# Nucleo_PCB_V1_1.net
KiCad netlist of a schematic drawn in Altium Designer
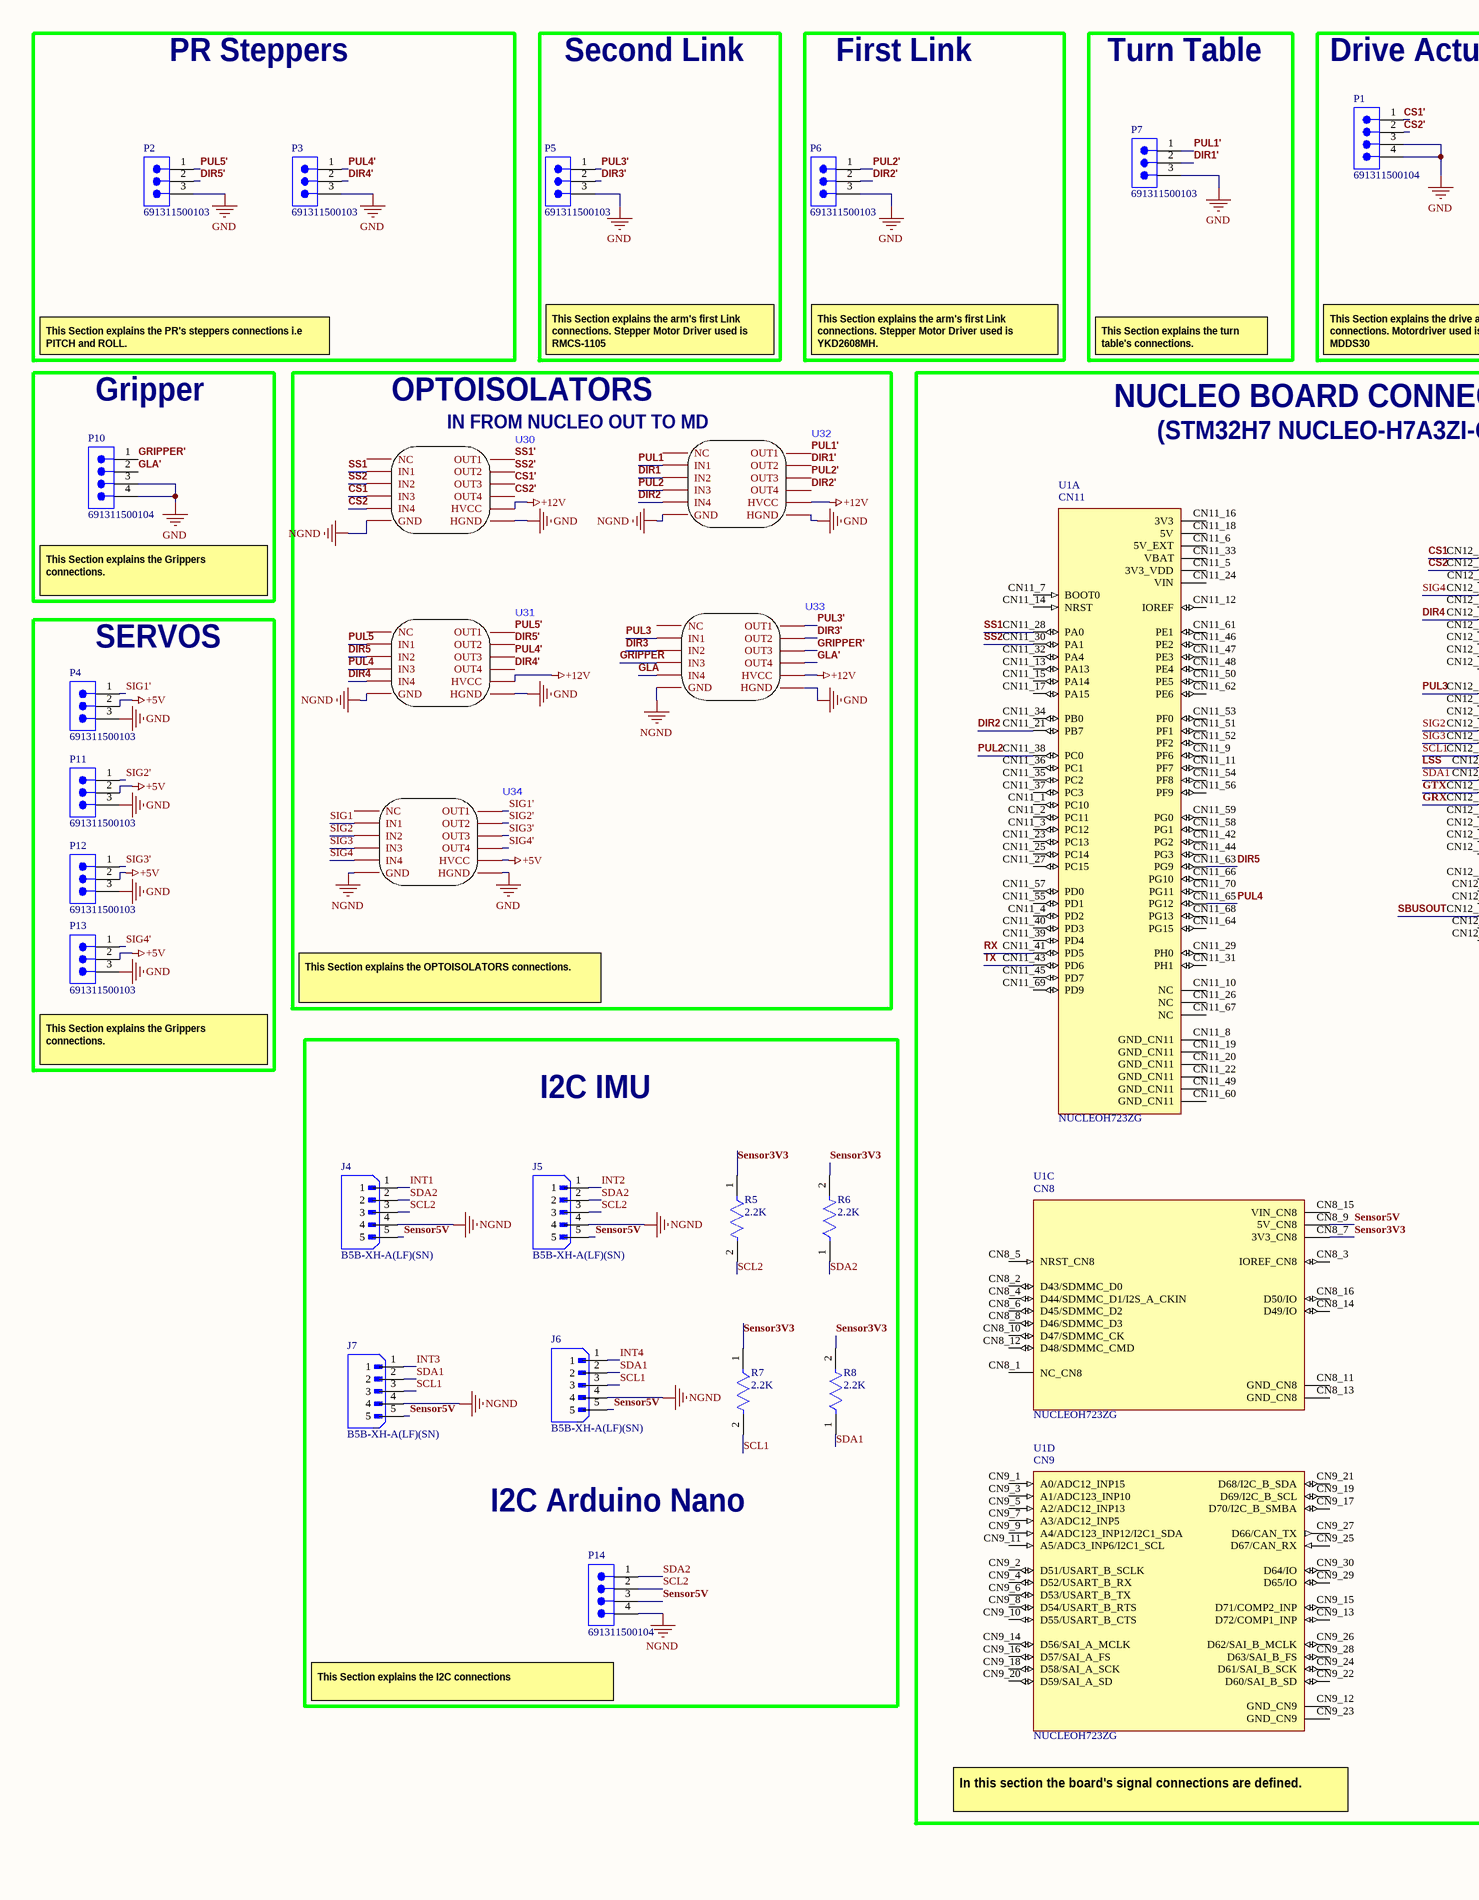
[diagram p0: Nucleo PCB V1.1.SchDoc, left]
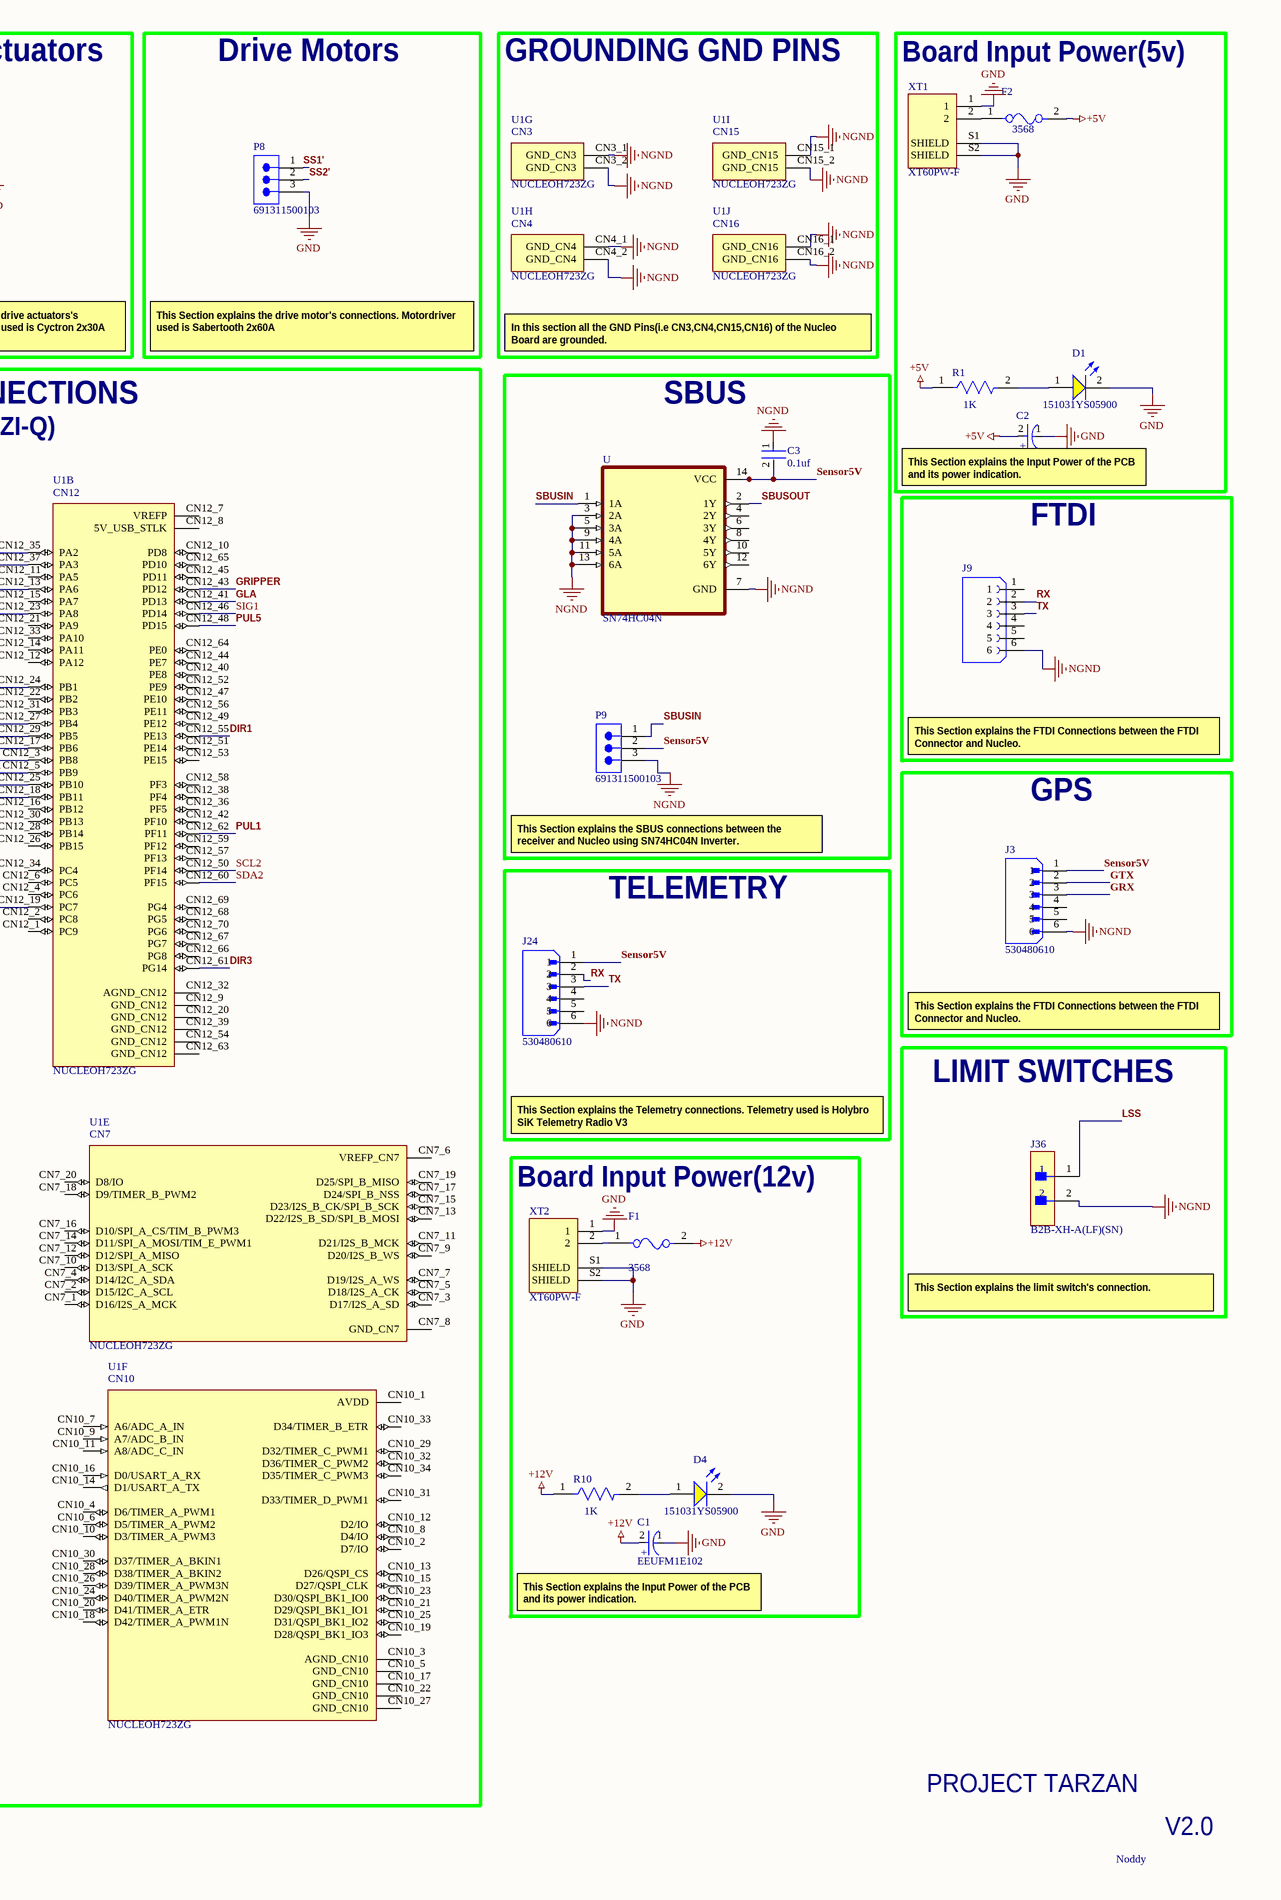
[diagram p1: Nucleo PCB V1.1.SchDoc, right]

(export (version "E")
  (design (tool "Eeschema 10.0.6"))
  (components
    (comp (ref "C1")
      (value "EEUFM1E102")
      (footprint "FP-RAD-TH-D_12_5_0_5-L_20-MFG")
      (description "Aluminum Electrolytic Capacitors (Radial Lead Type) 1000uF ±20% 25V")
      (fields (field (name "VOLTAGE") "25V") (field (name "TOLERANCE") "20%"))
      (libsource (lib "Altium Content Vault") (part "a00bbbee19879c290e62620ae7e47b1"))
    )
    (comp (ref "C2")
      (value "EEUFM1E102")
      (footprint "FP-RAD-TH-D_12_5_0_5-L_20-MFG")
      (description "Aluminum Electrolytic Capacitors (Radial Lead Type) 1000uF ±20% 25V")
      (fields (field (name "VOLTAGE") "25V") (field (name "TOLERANCE") "20%"))
      (libsource (lib "Altium Content Vault") (part "a00bbbee19879c290e62620ae7e47b1"))
    )
    (comp (ref "C3")
      (value "0.1uf")
      (footprint "FP-VY1472M63Y5UQ6TV0-MFG")
      (description "CAP CER 4700PF 760VAC Y5U RADIAL")
      (fields (field (name "TOLERANCE") "20%") (field (name "VOLTAGE") "500V"))
      (libsource (lib "Altium Content Vault") (part "11868f565c42a9108669ba33697ecf6"))
    )
    (comp (ref "D1")
      (value "151031YS05900")
      (footprint "WL-TMRC_D3.95H5.3")
      (libsource (lib "Altium Content Vault") (part "LED_Yellow_1A-2K"))
    )
    (comp (ref "D4")
      (value "151031YS05900")
      (footprint "WL-TMRC_D3.95H5.3")
      (libsource (lib "Altium Content Vault") (part "LED_Yellow_1A-2K"))
    )
    (comp (ref "F1")
      (value "3568")
      (footprint "FP-3568-MFG")
      (fields (field (name "VOLTAGE") "500V"))
      (libsource (lib "Altium Content Vault") (part "3568"))
    )
    (comp (ref "F2")
      (value "3568")
      (footprint "FP-3568-MFG")
      (fields (field (name "VOLTAGE") "500V"))
      (libsource (lib "Altium Content Vault") (part "3568"))
    )
    (comp (ref "J3")
      (value "530480610")
      (footprint "MOLEX_530480610")
      (libsource (lib "530480610") (part "530480610"))
    )
    (comp (ref "J4")
      (value "B5B-XH-A(LF)(SN)")
      (footprint "JST_B5B-XH-A(LF)(SN)")
      (description "Connector Header Through Hole 5 position 0.098 (2.50mm)")
      (fields (field (name "MF") "JST Sales America Inc."))
      (libsource (lib "B5B-XH-A_LF__SN_") (part "B5B-XH-A(LF)(SN)"))
    )
    (comp (ref "J5")
      (value "B5B-XH-A(LF)(SN)")
      (footprint "JST_B5B-XH-A(LF)(SN)")
      (description "Connector Header Through Hole 5 position 0.098 (2.50mm)")
      (fields (field (name "MF") "JST Sales America Inc."))
      (libsource (lib "B5B-XH-A_LF__SN_") (part "B5B-XH-A(LF)(SN)"))
    )
    (comp (ref "J6")
      (value "B5B-XH-A(LF)(SN)")
      (footprint "JST_B5B-XH-A(LF)(SN)")
      (description "Connector Header Through Hole 5 position 0.098 (2.50mm)")
      (fields (field (name "MF") "JST Sales America Inc."))
      (libsource (lib "B5B-XH-A_LF__SN_") (part "B5B-XH-A(LF)(SN)"))
    )
    (comp (ref "J7")
      (value "B5B-XH-A(LF)(SN)")
      (footprint "JST_B5B-XH-A(LF)(SN)")
      (description "Connector Header Through Hole 5 position 0.098 (2.50mm)")
      (fields (field (name "MF") "JST Sales America Inc."))
      (libsource (lib "B5B-XH-A_LF__SN_") (part "B5B-XH-A(LF)(SN)"))
    )
    (comp (ref "J9")
      (value "PPTC061LFBN-RC")
      (footprint "SULLINS_PPTC061LFBN-RC")
      (description "6 Position Header Connector 0.100 (2.54mm) Through Hole Tin")
      (fields (field (name "MF") "Sullins Connector"))
      (libsource (lib "PPTC061LFBN-RC") (part "PPTC061LFBN-RC"))
    )
    (comp (ref "J24")
      (value "530480610")
      (footprint "MOLEX_530480610")
      (libsource (lib "530480610") (part "530480610"))
    )
    (comp (ref "J36")
      (value "B2B-XH-A(LF)(SN)")
      (footprint "FP-B2B-XH-A_LF_SN-MFG")
      (description "CONN HEADER VERT 2POS 2.5MM")
      (libsource (lib "Altium Content Vault") (part "3bc925449376181038e59eaffc5286c"))
    )
    (comp (ref "P1")
      (value "691311500104")
      (footprint "691311500104")
      (fields (field (name "VOLTAGE") "300V"))
      (libsource (lib "Altium Content Vault") (part "TBL - 1R - 04P - Male"))
    )
    (comp (ref "P2")
      (value "691311500103")
      (footprint "691311500103")
      (fields (field (name "VOLTAGE") "300V"))
      (libsource (lib "Altium Content Vault") (part "TBL - 1R - 03P - Male"))
    )
    (comp (ref "P3")
      (value "691311500103")
      (footprint "691311500103")
      (fields (field (name "VOLTAGE") "300V"))
      (libsource (lib "Altium Content Vault") (part "TBL - 1R - 03P - Male"))
    )
    (comp (ref "P4")
      (value "691311500103")
      (footprint "691311500103")
      (fields (field (name "VOLTAGE") "300V"))
      (libsource (lib "Altium Content Vault") (part "TBL - 1R - 03P - Male"))
    )
    (comp (ref "P5")
      (value "691311500103")
      (footprint "691311500103")
      (fields (field (name "VOLTAGE") "300V"))
      (libsource (lib "Altium Content Vault") (part "TBL - 1R - 03P - Male"))
    )
    (comp (ref "P6")
      (value "691311500103")
      (footprint "691311500103")
      (fields (field (name "VOLTAGE") "300V"))
      (libsource (lib "Altium Content Vault") (part "TBL - 1R - 03P - Male"))
    )
    (comp (ref "P7")
      (value "691311500103")
      (footprint "691311500103")
      (fields (field (name "VOLTAGE") "300V"))
      (libsource (lib "Altium Content Vault") (part "TBL - 1R - 03P - Male"))
    )
    (comp (ref "P8")
      (value "691311500103")
      (footprint "691311500103")
      (fields (field (name "VOLTAGE") "300V"))
      (libsource (lib "Altium Content Vault") (part "TBL - 1R - 03P - Male"))
    )
    (comp (ref "P9")
      (value "691311500103")
      (footprint "691311500103")
      (fields (field (name "VOLTAGE") "300V"))
      (libsource (lib "Altium Content Vault") (part "TBL - 1R - 03P - Male"))
    )
    (comp (ref "P10")
      (value "691311500104")
      (footprint "691311500104")
      (fields (field (name "VOLTAGE") "300V"))
      (libsource (lib "Altium Content Vault") (part "TBL - 1R - 04P - Male"))
    )
    (comp (ref "P11")
      (value "691311500103")
      (footprint "691311500103")
      (fields (field (name "VOLTAGE") "300V"))
      (libsource (lib "Altium Content Vault") (part "TBL - 1R - 03P - Male"))
    )
    (comp (ref "P12")
      (value "691311500103")
      (footprint "691311500103")
      (fields (field (name "VOLTAGE") "300V"))
      (libsource (lib "Altium Content Vault") (part "TBL - 1R - 03P - Male"))
    )
    (comp (ref "P13")
      (value "691311500103")
      (footprint "691311500103")
      (fields (field (name "VOLTAGE") "300V"))
      (libsource (lib "Altium Content Vault") (part "TBL - 1R - 03P - Male"))
    )
    (comp (ref "P14")
      (value "691311500104")
      (footprint "691311500104")
      (fields (field (name "VOLTAGE") "300V"))
      (libsource (lib "Altium Content Vault") (part "TBL - 1R - 04P - Male"))
    )
    (comp (ref "R1")
      (value "1K")
      (footprint "FP-MRS25-MFG")
      (fields (field (name "TOLERANCE") "1%"))
      (libsource (lib "Altium Content Vault") (part "1029c3af85768c4190bb7ad29bc67b5"))
    )
    (comp (ref "R5")
      (value "2.2K")
      (footprint "FP-MRS25-MFG")
      (fields (field (name "TOLERANCE") "1%"))
      (libsource (lib "Altium Content Vault") (part "1029c3af85768c4190bb7ad29bc67b5"))
    )
    (comp (ref "R6")
      (value "2.2K")
      (footprint "FP-MRS25-MFG")
      (fields (field (name "TOLERANCE") "1%"))
      (libsource (lib "Altium Content Vault") (part "1029c3af85768c4190bb7ad29bc67b5"))
    )
    (comp (ref "R7")
      (value "2.2K")
      (footprint "FP-MRS25-MFG")
      (fields (field (name "TOLERANCE") "1%"))
      (libsource (lib "Altium Content Vault") (part "1029c3af85768c4190bb7ad29bc67b5"))
    )
    (comp (ref "R8")
      (value "2.2K")
      (footprint "FP-MRS25-MFG")
      (fields (field (name "TOLERANCE") "1%"))
      (libsource (lib "Altium Content Vault") (part "1029c3af85768c4190bb7ad29bc67b5"))
    )
    (comp (ref "R10")
      (value "1K")
      (footprint "FP-MRS25-MFG")
      (fields (field (name "TOLERANCE") "1%"))
      (libsource (lib "Altium Content Vault") (part "1029c3af85768c4190bb7ad29bc67b5"))
    )
    (comp (ref "U")
      (value "SN74HC04N")
      (footprint "DIP794W45P254L1969H508Q14")
      (description "Hex Inverters 14-PDIP -40 to 85")
      (fields
        (field (name "MF") "Texas Instruments")
        (field (name "BUYPART") "https://www.snapeda.com/parts/SN74HC04N/Texas%20Instruments/view-part/279498/?ref=eda")
      )
      (libsource (lib "SN74HC04N") (part "SN74HC04N"))
    )
    (comp (ref "U1")
      (value "NUCLEOH723ZG")
      (footprint "MODULE_NUCLEOH723ZG")
      (description "STM32H723ZG Nucleo-144 STM32H7 STM32 MCU 32-Bit Embedded Evaluation Board")
      (fields (field (name "MF") "STMicroelectronics"))
      (libsource (lib "APAC- Team Rudra-SRM Institute of Science and Technology") (part "NUCLEOH723ZG"))
    )
    (comp (ref "U30")
      (value "~")
      (footprint "TLP281-4 (4 CHANNEL OPTOISOLATOR)")
      (libsource (lib "altium-import") (part "root_0_TLP281-4 optoisolator module_vk_"))
    )
    (comp (ref "U31")
      (value "~")
      (footprint "TLP281-4 (4 CHANNEL OPTOISOLATOR)")
      (libsource (lib "altium-import") (part "root_0_TLP281-4 optoisolator module_vk_"))
    )
    (comp (ref "U32")
      (value "~")
      (footprint "TLP281-4 (4 CHANNEL OPTOISOLATOR)")
      (libsource (lib "altium-import") (part "root_0_TLP281-4 optoisolator module_vk_"))
    )
    (comp (ref "U33")
      (value "~")
      (footprint "TLP281-4 (4 CHANNEL OPTOISOLATOR)")
      (libsource (lib "altium-import") (part "root_0_TLP281-4 optoisolator module_vk_"))
    )
    (comp (ref "U34")
      (value "~")
      (footprint "TLP281-4 (4 CHANNEL OPTOISOLATOR)")
      (libsource (lib "altium-import") (part "root_0_TLP281-4 optoisolator module_vk_"))
    )
    (comp (ref "XT1")
      (value "XT60PW-F")
      (footprint "AMASS_XT60PW-F")
      (description "Socket DC Supply Connector Female")
      (fields (field (name "MF") "AMASS"))
      (libsource (lib "APAC- Team Rudra-SRM Institute of Science and Technology") (part "XT60PW-F"))
    )
    (comp (ref "XT2")
      (value "XT60PW-F")
      (footprint "AMASS_XT60PW-F")
      (description "Socket DC Supply Connector Female")
      (fields (field (name "MF") "AMASS"))
      (libsource (lib "APAC- Team Rudra-SRM Institute of Science and Technology") (part "XT60PW-F"))
    )
  )
  (nets
    (net (code "1") (name "+5V") (class "Default")
      (node (ref "C2") (pin "2") (pinfunction "A_2") (pintype "passive"))
      (node (ref "F2") (pin "2") (pinfunction "2_2") (pintype "passive"))
      (node (ref "P11") (pin "2") (pinfunction "2_2") (pintype "passive"))
      (node (ref "P12") (pin "2") (pinfunction "2_2") (pintype "passive"))
      (node (ref "P13") (pin "2") (pinfunction "2_2") (pintype "passive"))
      (node (ref "P4") (pin "2") (pinfunction "2_2") (pintype "passive"))
      (node (ref "R1") (pin "1") (pinfunction "1_1") (pintype "passive"))
      (node (ref "U34") (pin "5") (pinfunction "HVCC_5") (pintype "passive"))
    )
    (net (code "2") (name "+12V") (class "Default")
      (node (ref "C1") (pin "2") (pinfunction "A_2") (pintype "passive"))
      (node (ref "F1") (pin "2") (pinfunction "2_2") (pintype "passive"))
      (node (ref "R10") (pin "1") (pinfunction "1_1") (pintype "passive"))
      (node (ref "U30") (pin "5") (pinfunction "HVCC_5") (pintype "passive"))
      (node (ref "U31") (pin "5") (pinfunction "HVCC_5") (pintype "passive"))
      (node (ref "U32") (pin "5") (pinfunction "HVCC_5") (pintype "passive"))
      (node (ref "U33") (pin "5") (pinfunction "HVCC_5") (pintype "passive"))
    )
    (net (code "3") (name "/CS1") (class "Default")
      (node (ref "U1") (pin "CN12_35") (pinfunction "PA2_CN12_35") (pintype "bidirectional"))
      (node (ref "U30") (pin "9") (pinfunction "IN3_9") (pintype "passive"))
    )
    (net (code "4") (name "/CS1'") (class "Default")
      (node (ref "P1") (pin "1") (pinfunction "1_1") (pintype "passive"))
      (node (ref "U30") (pin "3") (pinfunction "OUT3_3") (pintype "passive"))
    )
    (net (code "5") (name "/CS2") (class "Default")
      (node (ref "U1") (pin "CN12_37") (pinfunction "PA3_CN12_37") (pintype "bidirectional"))
      (node (ref "U30") (pin "8") (pinfunction "IN4_8") (pintype "passive"))
    )
    (net (code "6") (name "/CS2'") (class "Default")
      (node (ref "P1") (pin "2") (pinfunction "2_2") (pintype "passive"))
      (node (ref "U30") (pin "4") (pinfunction "OUT4_4") (pintype "passive"))
    )
    (net (code "7") (name "/DIR1") (class "Default")
      (node (ref "U1") (pin "CN12_55") (pinfunction "PE13_CN12_55") (pintype "bidirectional"))
      (node (ref "U32") (pin "10") (pinfunction "IN2_10") (pintype "passive"))
    )
    (net (code "8") (name "/DIR1'") (class "Default")
      (node (ref "P7") (pin "2") (pinfunction "2_2") (pintype "passive"))
      (node (ref "U32") (pin "2") (pinfunction "OUT2_2") (pintype "passive"))
    )
    (net (code "9") (name "/DIR2") (class "Default")
      (node (ref "U1") (pin "CN11_21") (pinfunction "PB7_CN11_21") (pintype "bidirectional"))
      (node (ref "U32") (pin "8") (pinfunction "IN4_8") (pintype "passive"))
    )
    (net (code "10") (name "/DIR2'") (class "Default")
      (node (ref "P6") (pin "2") (pinfunction "2_2") (pintype "passive"))
      (node (ref "U32") (pin "4") (pinfunction "OUT4_4") (pintype "passive"))
    )
    (net (code "11") (name "/DIR3") (class "Default")
      (node (ref "U1") (pin "CN12_61") (pinfunction "PG14_CN12_61") (pintype "bidirectional"))
      (node (ref "U33") (pin "10") (pinfunction "IN2_10") (pintype "passive"))
    )
    (net (code "12") (name "/DIR3'") (class "Default")
      (node (ref "P5") (pin "2") (pinfunction "2_2") (pintype "passive"))
      (node (ref "U33") (pin "2") (pinfunction "OUT2_2") (pintype "passive"))
    )
    (net (code "13") (name "/DIR4") (class "Default")
      (node (ref "U1") (pin "CN12_23") (pinfunction "PA8_CN12_23") (pintype "bidirectional"))
      (node (ref "U31") (pin "8") (pinfunction "IN4_8") (pintype "passive"))
    )
    (net (code "14") (name "/DIR4'") (class "Default")
      (node (ref "P3") (pin "2") (pinfunction "2_2") (pintype "passive"))
      (node (ref "U31") (pin "4") (pinfunction "OUT4_4") (pintype "passive"))
    )
    (net (code "15") (name "/DIR5") (class "Default")
      (node (ref "U1") (pin "CN11_63") (pinfunction "PG9_CN11_63") (pintype "bidirectional"))
      (node (ref "U31") (pin "10") (pinfunction "IN2_10") (pintype "passive"))
    )
    (net (code "16") (name "/DIR5'") (class "Default")
      (node (ref "P2") (pin "2") (pinfunction "2_2") (pintype "passive"))
      (node (ref "U31") (pin "2") (pinfunction "OUT2_2") (pintype "passive"))
    )
    (net (code "17") (name "/GLA") (class "Default")
      (node (ref "U1") (pin "CN12_41") (pinfunction "PD13_CN12_41") (pintype "bidirectional"))
      (node (ref "U33") (pin "8") (pinfunction "IN4_8") (pintype "passive"))
    )
    (net (code "18") (name "/GLA'") (class "Default")
      (node (ref "P10") (pin "2") (pinfunction "2_2") (pintype "passive"))
      (node (ref "U33") (pin "4") (pinfunction "OUT4_4") (pintype "passive"))
    )
    (net (code "19") (name "/GRIPPER") (class "Default")
      (node (ref "U1") (pin "CN12_43") (pinfunction "PD12_CN12_43") (pintype "bidirectional"))
      (node (ref "U33") (pin "9") (pinfunction "IN3_9") (pintype "passive"))
    )
    (net (code "20") (name "/GRIPPER'") (class "Default")
      (node (ref "P10") (pin "1") (pinfunction "1_1") (pintype "passive"))
      (node (ref "U33") (pin "3") (pinfunction "OUT3_3") (pintype "passive"))
    )
    (net (code "21") (name "/GRX") (class "Default")
      (node (ref "J3") (pin "3") (pinfunction "3_3") (pintype "passive"))
      (node (ref "U1") (pin "CN12_18") (pinfunction "PB11_CN12_18") (pintype "bidirectional"))
    )
    (net (code "22") (name "/GTX") (class "Default")
      (node (ref "J3") (pin "2") (pinfunction "2_2") (pintype "passive"))
      (node (ref "U1") (pin "CN12_25") (pinfunction "PB10_CN12_25") (pintype "bidirectional"))
    )
    (net (code "23") (name "/INT1") (class "Default")
      (node (ref "J4") (pin "1") (pinfunction "1_1") (pintype "passive"))
    )
    (net (code "24") (name "/INT2") (class "Default")
      (node (ref "J5") (pin "1") (pinfunction "1_1") (pintype "passive"))
    )
    (net (code "25") (name "/INT3") (class "Default")
      (node (ref "J7") (pin "1") (pinfunction "1_1") (pintype "passive"))
    )
    (net (code "26") (name "/INT4") (class "Default")
      (node (ref "J6") (pin "1") (pinfunction "1_1") (pintype "passive"))
    )
    (net (code "27") (name "/LSS") (class "Default")
      (node (ref "J36") (pin "1") (pinfunction "1_1") (pintype "passive"))
      (node (ref "U1") (pin "CN12_3") (pinfunction "PB8_CN12_3") (pintype "bidirectional"))
    )
    (net (code "28") (name "/PUL1") (class "Default")
      (node (ref "U1") (pin "CN12_62") (pinfunction "PF11_CN12_62") (pintype "bidirectional"))
      (node (ref "U32") (pin "11") (pinfunction "IN1_11") (pintype "passive"))
    )
    (net (code "29") (name "/PUL1'") (class "Default")
      (node (ref "P7") (pin "1") (pinfunction "1_1") (pintype "passive"))
      (node (ref "U32") (pin "1") (pinfunction "OUT1_1") (pintype "passive"))
    )
    (net (code "30") (name "/PUL2") (class "Default")
      (node (ref "U1") (pin "CN11_38") (pinfunction "PC0_CN11_38") (pintype "bidirectional"))
      (node (ref "U32") (pin "9") (pinfunction "IN3_9") (pintype "passive"))
    )
    (net (code "31") (name "/PUL2'") (class "Default")
      (node (ref "P6") (pin "1") (pinfunction "1_1") (pintype "passive"))
      (node (ref "U32") (pin "3") (pinfunction "OUT3_3") (pintype "passive"))
    )
    (net (code "32") (name "/PUL3") (class "Default")
      (node (ref "U1") (pin "CN12_24") (pinfunction "PB1_CN12_24") (pintype "bidirectional"))
      (node (ref "U33") (pin "11") (pinfunction "IN1_11") (pintype "passive"))
    )
    (net (code "33") (name "/PUL3'") (class "Default")
      (node (ref "P5") (pin "1") (pinfunction "1_1") (pintype "passive"))
      (node (ref "U33") (pin "1") (pinfunction "OUT1_1") (pintype "passive"))
    )
    (net (code "34") (name "/PUL4") (class "Default")
      (node (ref "U1") (pin "CN11_65") (pinfunction "PG12_CN11_65") (pintype "bidirectional"))
      (node (ref "U31") (pin "9") (pinfunction "IN3_9") (pintype "passive"))
    )
    (net (code "35") (name "/PUL4'") (class "Default")
      (node (ref "P3") (pin "1") (pinfunction "1_1") (pintype "passive"))
      (node (ref "U31") (pin "3") (pinfunction "OUT3_3") (pintype "passive"))
    )
    (net (code "36") (name "/PUL5") (class "Default")
      (node (ref "U1") (pin "CN12_48") (pinfunction "PD15_CN12_48") (pintype "bidirectional"))
      (node (ref "U31") (pin "11") (pinfunction "IN1_11") (pintype "passive"))
    )
    (net (code "37") (name "/PUL5'") (class "Default")
      (node (ref "P2") (pin "1") (pinfunction "1_1") (pintype "passive"))
      (node (ref "U31") (pin "1") (pinfunction "OUT1_1") (pintype "passive"))
    )
    (net (code "38") (name "/RX") (class "Default")
      (node (ref "J24") (pin "2") (pinfunction "2_2") (pintype "passive"))
      (node (ref "J9") (pin "2") (pinfunction "2_2") (pintype "passive"))
      (node (ref "U1") (pin "CN11_41") (pinfunction "PD5_CN11_41") (pintype "bidirectional"))
    )
    (net (code "39") (name "/SBUSIN") (class "Default")
      (node (ref "P9") (pin "1") (pinfunction "1_1") (pintype "passive"))
      (node (ref "U") (pin "1") (pinfunction "1A_1") (pintype "input"))
    )
    (net (code "40") (name "/SBUSOUT") (class "Default")
      (node (ref "U") (pin "2") (pinfunction "1Y_2") (pintype "output"))
      (node (ref "U1") (pin "CN12_19") (pinfunction "PC7_CN12_19") (pintype "bidirectional"))
    )
    (net (code "41") (name "/SCL1") (class "Default")
      (node (ref "J6") (pin "3") (pinfunction "3_3") (pintype "passive"))
      (node (ref "J7") (pin "3") (pinfunction "3_3") (pintype "passive"))
      (node (ref "R7") (pin "2") (pinfunction "2_2") (pintype "passive"))
      (node (ref "U1") (pin "CN12_17") (pinfunction "PB6_CN12_17") (pintype "bidirectional"))
    )
    (net (code "42") (name "/SCL2") (class "Default")
      (node (ref "J4") (pin "3") (pinfunction "3_3") (pintype "passive"))
      (node (ref "J5") (pin "3") (pinfunction "3_3") (pintype "passive"))
      (node (ref "P14") (pin "2") (pinfunction "2_2") (pintype "passive"))
      (node (ref "R5") (pin "2") (pinfunction "2_2") (pintype "passive"))
      (node (ref "U1") (pin "CN12_50") (pinfunction "PF14_CN12_50") (pintype "bidirectional"))
    )
    (net (code "43") (name "/SDA1") (class "Default")
      (node (ref "J6") (pin "2") (pinfunction "2_2") (pintype "passive"))
      (node (ref "J7") (pin "2") (pinfunction "2_2") (pintype "passive"))
      (node (ref "R8") (pin "1") (pinfunction "1_1") (pintype "passive"))
      (node (ref "U1") (pin "CN12_5") (pinfunction "PB9_CN12_5") (pintype "bidirectional"))
    )
    (net (code "44") (name "/SDA2") (class "Default")
      (node (ref "J4") (pin "2") (pinfunction "2_2") (pintype "passive"))
      (node (ref "J5") (pin "2") (pinfunction "2_2") (pintype "passive"))
      (node (ref "P14") (pin "1") (pinfunction "1_1") (pintype "passive"))
      (node (ref "R6") (pin "1") (pinfunction "1_1") (pintype "passive"))
      (node (ref "U1") (pin "CN12_60") (pinfunction "PF15_CN12_60") (pintype "bidirectional"))
    )
    (net (code "45") (name "/SIG1") (class "Default")
      (node (ref "U1") (pin "CN12_46") (pinfunction "PD14_CN12_46") (pintype "bidirectional"))
      (node (ref "U34") (pin "11") (pinfunction "IN1_11") (pintype "passive"))
    )
    (net (code "46") (name "/SIG1'") (class "Default")
      (node (ref "P4") (pin "1") (pinfunction "1_1") (pintype "passive"))
      (node (ref "U34") (pin "1") (pinfunction "OUT1_1") (pintype "passive"))
    )
    (net (code "47") (name "/SIG2") (class "Default")
      (node (ref "U1") (pin "CN12_27") (pinfunction "PB4_CN12_27") (pintype "bidirectional"))
      (node (ref "U34") (pin "10") (pinfunction "IN2_10") (pintype "passive"))
    )
    (net (code "48") (name "/SIG2'") (class "Default")
      (node (ref "P11") (pin "1") (pinfunction "1_1") (pintype "passive"))
      (node (ref "U34") (pin "2") (pinfunction "OUT2_2") (pintype "passive"))
    )
    (net (code "49") (name "/SIG3") (class "Default")
      (node (ref "U1") (pin "CN12_29") (pinfunction "PB5_CN12_29") (pintype "bidirectional"))
      (node (ref "U34") (pin "9") (pinfunction "IN3_9") (pintype "passive"))
    )
    (net (code "50") (name "/SIG3'") (class "Default")
      (node (ref "P12") (pin "1") (pinfunction "1_1") (pintype "passive"))
      (node (ref "U34") (pin "3") (pinfunction "OUT3_3") (pintype "passive"))
    )
    (net (code "51") (name "/SIG4") (class "Default")
      (node (ref "U1") (pin "CN12_13") (pinfunction "PA6_CN12_13") (pintype "bidirectional"))
      (node (ref "U34") (pin "8") (pinfunction "IN4_8") (pintype "passive"))
    )
    (net (code "52") (name "/SIG4'") (class "Default")
      (node (ref "P13") (pin "1") (pinfunction "1_1") (pintype "passive"))
      (node (ref "U34") (pin "4") (pinfunction "OUT4_4") (pintype "passive"))
    )
    (net (code "53") (name "/SS1") (class "Default")
      (node (ref "U1") (pin "CN11_28") (pinfunction "PA0_CN11_28") (pintype "bidirectional"))
      (node (ref "U30") (pin "11") (pinfunction "IN1_11") (pintype "passive"))
    )
    (net (code "54") (name "/SS1'") (class "Default")
      (node (ref "P8") (pin "1") (pinfunction "1_1") (pintype "passive"))
      (node (ref "U30") (pin "1") (pinfunction "OUT1_1") (pintype "passive"))
    )
    (net (code "55") (name "/SS2") (class "Default")
      (node (ref "U1") (pin "CN11_30") (pinfunction "PA1_CN11_30") (pintype "bidirectional"))
      (node (ref "U30") (pin "10") (pinfunction "IN2_10") (pintype "passive"))
    )
    (net (code "56") (name "/SS2'") (class "Default")
      (node (ref "P8") (pin "2") (pinfunction "2_2") (pintype "passive"))
      (node (ref "U30") (pin "2") (pinfunction "OUT2_2") (pintype "passive"))
    )
    (net (code "57") (name "/Sensor3V3") (class "Default")
      (node (ref "R5") (pin "1") (pinfunction "1_1") (pintype "passive"))
      (node (ref "R6") (pin "2") (pinfunction "2_2") (pintype "passive"))
      (node (ref "R7") (pin "1") (pinfunction "1_1") (pintype "passive"))
      (node (ref "R8") (pin "2") (pinfunction "2_2") (pintype "passive"))
      (node (ref "U1") (pin "CN8_7") (pinfunction "3V3_CN8_CN8_7") (pintype "power_in"))
    )
    (net (code "58") (name "/Sensor5V") (class "Default")
      (node (ref "C3") (pin "2") (pinfunction "2_2") (pintype "passive"))
      (node (ref "J24") (pin "1") (pinfunction "1_1") (pintype "passive"))
      (node (ref "J3") (pin "1") (pinfunction "1_1") (pintype "passive"))
      (node (ref "J4") (pin "5") (pinfunction "5_5") (pintype "passive"))
      (node (ref "J5") (pin "5") (pinfunction "5_5") (pintype "passive"))
      (node (ref "J6") (pin "5") (pinfunction "5_5") (pintype "passive"))
      (node (ref "J7") (pin "5") (pinfunction "5_5") (pintype "passive"))
      (node (ref "P14") (pin "3") (pinfunction "3_3") (pintype "passive"))
      (node (ref "P9") (pin "2") (pinfunction "2_2") (pintype "passive"))
      (node (ref "U") (pin "14") (pinfunction "VCC_14") (pintype "power_in"))
      (node (ref "U1") (pin "CN8_9") (pinfunction "5V_CN8_CN8_9") (pintype "power_in"))
    )
    (net (code "59") (name "/TX") (class "Default")
      (node (ref "J24") (pin "3") (pinfunction "3_3") (pintype "passive"))
      (node (ref "J9") (pin "3") (pinfunction "3_3") (pintype "passive"))
      (node (ref "U1") (pin "CN11_43") (pinfunction "PD6_CN11_43") (pintype "bidirectional"))
    )
    (net (code "60") (name "GND") (class "Default")
      (node (ref "C1") (pin "1") (pinfunction "C_1") (pintype "passive"))
      (node (ref "C2") (pin "1") (pinfunction "C_1") (pintype "passive"))
      (node (ref "D1") (pin "2") (pinfunction "K_2") (pintype "passive"))
      (node (ref "D4") (pin "2") (pinfunction "K_2") (pintype "passive"))
      (node (ref "P1") (pin "3") (pinfunction "3_3") (pintype "passive"))
      (node (ref "P1") (pin "4") (pinfunction "4_4") (pintype "passive"))
      (node (ref "P10") (pin "3") (pinfunction "3_3") (pintype "passive"))
      (node (ref "P10") (pin "4") (pinfunction "4_4") (pintype "passive"))
      (node (ref "P11") (pin "3") (pinfunction "3_3") (pintype "passive"))
      (node (ref "P12") (pin "3") (pinfunction "3_3") (pintype "passive"))
      (node (ref "P13") (pin "3") (pinfunction "3_3") (pintype "passive"))
      (node (ref "P2") (pin "3") (pinfunction "3_3") (pintype "passive"))
      (node (ref "P3") (pin "3") (pinfunction "3_3") (pintype "passive"))
      (node (ref "P4") (pin "3") (pinfunction "3_3") (pintype "passive"))
      (node (ref "P5") (pin "3") (pinfunction "3_3") (pintype "passive"))
      (node (ref "P6") (pin "3") (pinfunction "3_3") (pintype "passive"))
      (node (ref "P7") (pin "3") (pinfunction "3_3") (pintype "passive"))
      (node (ref "P8") (pin "3") (pinfunction "3_3") (pintype "passive"))
      (node (ref "U30") (pin "6") (pinfunction "HGND_6") (pintype "passive"))
      (node (ref "U31") (pin "6") (pinfunction "HGND_6") (pintype "passive"))
      (node (ref "U32") (pin "6") (pinfunction "HGND_6") (pintype "passive"))
      (node (ref "U33") (pin "6") (pinfunction "HGND_6") (pintype "passive"))
      (node (ref "U34") (pin "6") (pinfunction "HGND_6") (pintype "passive"))
      (node (ref "XT1") (pin "1") (pinfunction "1_1") (pintype "passive"))
      (node (ref "XT1") (pin "S1") (pinfunction "SHIELD_S1") (pintype "passive"))
      (node (ref "XT1") (pin "S2") (pinfunction "SHIELD_S2") (pintype "passive"))
      (node (ref "XT2") (pin "1") (pinfunction "1_1") (pintype "passive"))
      (node (ref "XT2") (pin "S1") (pinfunction "SHIELD_S1") (pintype "passive"))
      (node (ref "XT2") (pin "S2") (pinfunction "SHIELD_S2") (pintype "passive"))
    )
    (net (code "61") (name "NGND") (class "Default")
      (node (ref "C3") (pin "1") (pinfunction "1_1") (pintype "passive"))
      (node (ref "J24") (pin "6") (pinfunction "6_6") (pintype "passive"))
      (node (ref "J3") (pin "6") (pinfunction "6_6") (pintype "passive"))
      (node (ref "J36") (pin "2") (pinfunction "2_2") (pintype "passive"))
      (node (ref "J4") (pin "4") (pinfunction "4_4") (pintype "passive"))
      (node (ref "J5") (pin "4") (pinfunction "4_4") (pintype "passive"))
      (node (ref "J6") (pin "4") (pinfunction "4_4") (pintype "passive"))
      (node (ref "J7") (pin "4") (pinfunction "4_4") (pintype "passive"))
      (node (ref "J9") (pin "6") (pinfunction "6_6") (pintype "passive"))
      (node (ref "P14") (pin "4") (pinfunction "4_4") (pintype "passive"))
      (node (ref "P9") (pin "3") (pinfunction "3_3") (pintype "passive"))
      (node (ref "U") (pin "11") (pinfunction "5A_11") (pintype "input"))
      (node (ref "U") (pin "13") (pinfunction "6A_13") (pintype "input"))
      (node (ref "U") (pin "3") (pinfunction "2A_3") (pintype "input"))
      (node (ref "U") (pin "5") (pinfunction "3A_5") (pintype "input"))
      (node (ref "U") (pin "7") (pinfunction "GND_7") (pintype "power_in"))
      (node (ref "U") (pin "9") (pinfunction "4A_9") (pintype "input"))
      (node (ref "U1") (pin "CN15_1") (pinfunction "GND_CN15_CN15_1") (pintype "power_in"))
      (node (ref "U1") (pin "CN15_2") (pinfunction "GND_CN15_CN15_2") (pintype "power_in"))
      (node (ref "U1") (pin "CN16_1") (pinfunction "GND_CN16_CN16_1") (pintype "power_in"))
      (node (ref "U1") (pin "CN16_2") (pinfunction "GND_CN16_CN16_2") (pintype "power_in"))
      (node (ref "U1") (pin "CN3_1") (pinfunction "GND_CN3_CN3_1") (pintype "power_in"))
      (node (ref "U1") (pin "CN3_2") (pinfunction "GND_CN3_CN3_2") (pintype "power_in"))
      (node (ref "U1") (pin "CN4_1") (pinfunction "GND_CN4_CN4_1") (pintype "power_in"))
      (node (ref "U1") (pin "CN4_2") (pinfunction "GND_CN4_CN4_2") (pintype "power_in"))
      (node (ref "U30") (pin "7") (pinfunction "GND_7") (pintype "passive"))
      (node (ref "U31") (pin "7") (pinfunction "GND_7") (pintype "passive"))
      (node (ref "U32") (pin "7") (pinfunction "GND_7") (pintype "passive"))
      (node (ref "U33") (pin "7") (pinfunction "GND_7") (pintype "passive"))
      (node (ref "U34") (pin "7") (pinfunction "GND_7") (pintype "passive"))
    )
    (net (code "62") (name "Net-(D1-A)") (class "Default")
      (node (ref "D1") (pin "1") (pinfunction "A_1") (pintype "passive"))
      (node (ref "R1") (pin "2") (pinfunction "2_2") (pintype "passive"))
    )
    (net (code "63") (name "Net-(D4-A)") (class "Default")
      (node (ref "D4") (pin "1") (pinfunction "A_1") (pintype "passive"))
      (node (ref "R10") (pin "2") (pinfunction "2_2") (pintype "passive"))
    )
    (net (code "64") (name "Net-(F1-Pad1)") (class "Default")
      (node (ref "F1") (pin "1") (pinfunction "1_1") (pintype "passive"))
      (node (ref "XT2") (pin "2") (pinfunction "2_2") (pintype "passive"))
    )
    (net (code "65") (name "Net-(F2-Pad1)") (class "Default")
      (node (ref "F2") (pin "1") (pinfunction "1_1") (pintype "passive"))
      (node (ref "XT1") (pin "2") (pinfunction "2_2") (pintype "passive"))
    )
    (net (code "66") (name "unconnected-(J3-Pad4)") (class "Default")
      (node (ref "J3") (pin "4") (pinfunction "4_4") (pintype "passive"))
    )
    (net (code "67") (name "unconnected-(J3-Pad5)") (class "Default")
      (node (ref "J3") (pin "5") (pinfunction "5_5") (pintype "passive"))
    )
    (net (code "68") (name "unconnected-(J9-Pad1)") (class "Default")
      (node (ref "J9") (pin "1") (pinfunction "1_1") (pintype "passive"))
    )
    (net (code "69") (name "unconnected-(J9-Pad4)") (class "Default")
      (node (ref "J9") (pin "4") (pinfunction "4_4") (pintype "passive"))
    )
    (net (code "70") (name "unconnected-(J9-Pad5)") (class "Default")
      (node (ref "J9") (pin "5") (pinfunction "5_5") (pintype "passive"))
    )
    (net (code "71") (name "unconnected-(J24-Pad4)") (class "Default")
      (node (ref "J24") (pin "4") (pinfunction "4_4") (pintype "passive"))
    )
    (net (code "72") (name "unconnected-(J24-Pad5)") (class "Default")
      (node (ref "J24") (pin "5") (pinfunction "5_5") (pintype "passive"))
    )
    (net (code "73") (name "unconnected-(U-2Y-Pad4)") (class "Default")
      (node (ref "U") (pin "4") (pinfunction "2Y_4") (pintype "output"))
    )
    (net (code "74") (name "unconnected-(U-3Y-Pad6)") (class "Default")
      (node (ref "U") (pin "6") (pinfunction "3Y_6") (pintype "output"))
    )
    (net (code "75") (name "unconnected-(U-4Y-Pad8)") (class "Default")
      (node (ref "U") (pin "8") (pinfunction "4Y_8") (pintype "output"))
    )
    (net (code "76") (name "unconnected-(U-5Y-Pad10)") (class "Default")
      (node (ref "U") (pin "10") (pinfunction "5Y_10") (pintype "output"))
    )
    (net (code "77") (name "unconnected-(U-6Y-Pad12)") (class "Default")
      (node (ref "U") (pin "12") (pinfunction "6Y_12") (pintype "output"))
    )
    (net (code "78") (name "unconnected-(U1A-3V3-PadCN11_16)") (class "Default")
      (node (ref "U1") (pin "CN11_16") (pinfunction "3V3_CN11_16") (pintype "power_in"))
    )
    (net (code "79") (name "unconnected-(U1A-3V3_VDD-PadCN11_5)") (class "Default")
      (node (ref "U1") (pin "CN11_5") (pinfunction "3V3_VDD_CN11_5") (pintype "power_in"))
    )
    (net (code "80") (name "unconnected-(U1A-5V-PadCN11_18)") (class "Default")
      (node (ref "U1") (pin "CN11_18") (pinfunction "5V_CN11_18") (pintype "power_in"))
    )
    (net (code "81") (name "unconnected-(U1A-5V_EXT-PadCN11_6)") (class "Default")
      (node (ref "U1") (pin "CN11_6") (pinfunction "5V_EXT_CN11_6") (pintype "power_in"))
    )
    (net (code "82") (name "unconnected-(U1A-BOOT0-PadCN11_7)") (class "Default")
      (node (ref "U1") (pin "CN11_7") (pinfunction "BOOT0_CN11_7") (pintype "input"))
    )
    (net (code "83") (name "unconnected-(U1A-GND_CN11-PadCN11_8)") (class "Default")
      (node (ref "U1") (pin "CN11_8") (pinfunction "GND_CN11_CN11_8") (pintype "power_in"))
    )
    (net (code "84") (name "unconnected-(U1A-GND_CN11-PadCN11_19)") (class "Default")
      (node (ref "U1") (pin "CN11_19") (pinfunction "GND_CN11_CN11_19") (pintype "power_in"))
    )
    (net (code "85") (name "unconnected-(U1A-GND_CN11-PadCN11_20)") (class "Default")
      (node (ref "U1") (pin "CN11_20") (pinfunction "GND_CN11_CN11_20") (pintype "power_in"))
    )
    (net (code "86") (name "unconnected-(U1A-GND_CN11-PadCN11_22)") (class "Default")
      (node (ref "U1") (pin "CN11_22") (pinfunction "GND_CN11_CN11_22") (pintype "power_in"))
    )
    (net (code "87") (name "unconnected-(U1A-GND_CN11-PadCN11_49)") (class "Default")
      (node (ref "U1") (pin "CN11_49") (pinfunction "GND_CN11_CN11_49") (pintype "power_in"))
    )
    (net (code "88") (name "unconnected-(U1A-GND_CN11-PadCN11_60)") (class "Default")
      (node (ref "U1") (pin "CN11_60") (pinfunction "GND_CN11_CN11_60") (pintype "power_in"))
    )
    (net (code "89") (name "unconnected-(U1A-IOREF-PadCN11_12)") (class "Default")
      (node (ref "U1") (pin "CN11_12") (pinfunction "IOREF_CN11_12") (pintype "bidirectional"))
    )
    (net (code "90") (name "unconnected-(U1A-NC-PadCN11_10)") (class "Default")
      (node (ref "U1") (pin "CN11_10") (pinfunction "NC_CN11_10") (pintype "passive"))
    )
    (net (code "91") (name "unconnected-(U1A-NC-PadCN11_26)") (class "Default")
      (node (ref "U1") (pin "CN11_26") (pinfunction "NC_CN11_26") (pintype "passive"))
    )
    (net (code "92") (name "unconnected-(U1A-NC-PadCN11_67)") (class "Default")
      (node (ref "U1") (pin "CN11_67") (pinfunction "NC_CN11_67") (pintype "passive"))
    )
    (net (code "93") (name "unconnected-(U1A-NRST-PadCN11_14)") (class "Default")
      (node (ref "U1") (pin "CN11_14") (pinfunction "NRST_CN11_14") (pintype "input"))
    )
    (net (code "94") (name "unconnected-(U1A-PA4-PadCN11_32)") (class "Default")
      (node (ref "U1") (pin "CN11_32") (pinfunction "PA4_CN11_32") (pintype "bidirectional"))
    )
    (net (code "95") (name "unconnected-(U1A-PA13-PadCN11_13)") (class "Default")
      (node (ref "U1") (pin "CN11_13") (pinfunction "PA13_CN11_13") (pintype "bidirectional"))
    )
    (net (code "96") (name "unconnected-(U1A-PA14-PadCN11_15)") (class "Default")
      (node (ref "U1") (pin "CN11_15") (pinfunction "PA14_CN11_15") (pintype "bidirectional"))
    )
    (net (code "97") (name "unconnected-(U1A-PA15-PadCN11_17)") (class "Default")
      (node (ref "U1") (pin "CN11_17") (pinfunction "PA15_CN11_17") (pintype "bidirectional"))
    )
    (net (code "98") (name "unconnected-(U1A-PB0-PadCN11_34)") (class "Default")
      (node (ref "U1") (pin "CN11_34") (pinfunction "PB0_CN11_34") (pintype "bidirectional"))
    )
    (net (code "99") (name "unconnected-(U1A-PC1-PadCN11_36)") (class "Default")
      (node (ref "U1") (pin "CN11_36") (pinfunction "PC1_CN11_36") (pintype "bidirectional"))
    )
    (net (code "100") (name "unconnected-(U1A-PC2-PadCN11_35)") (class "Default")
      (node (ref "U1") (pin "CN11_35") (pinfunction "PC2_CN11_35") (pintype "bidirectional"))
    )
    (net (code "101") (name "unconnected-(U1A-PC3-PadCN11_37)") (class "Default")
      (node (ref "U1") (pin "CN11_37") (pinfunction "PC3_CN11_37") (pintype "bidirectional"))
    )
    (net (code "102") (name "unconnected-(U1A-PC10-PadCN11_1)") (class "Default")
      (node (ref "U1") (pin "CN11_1") (pinfunction "PC10_CN11_1") (pintype "bidirectional"))
    )
    (net (code "103") (name "unconnected-(U1A-PC11-PadCN11_2)") (class "Default")
      (node (ref "U1") (pin "CN11_2") (pinfunction "PC11_CN11_2") (pintype "bidirectional"))
    )
    (net (code "104") (name "unconnected-(U1A-PC12-PadCN11_3)") (class "Default")
      (node (ref "U1") (pin "CN11_3") (pinfunction "PC12_CN11_3") (pintype "bidirectional"))
    )
    (net (code "105") (name "unconnected-(U1A-PC13-PadCN11_23)") (class "Default")
      (node (ref "U1") (pin "CN11_23") (pinfunction "PC13_CN11_23") (pintype "bidirectional"))
    )
    (net (code "106") (name "unconnected-(U1A-PC14-PadCN11_25)") (class "Default")
      (node (ref "U1") (pin "CN11_25") (pinfunction "PC14_CN11_25") (pintype "bidirectional"))
    )
    (net (code "107") (name "unconnected-(U1A-PC15-PadCN11_27)") (class "Default")
      (node (ref "U1") (pin "CN11_27") (pinfunction "PC15_CN11_27") (pintype "bidirectional"))
    )
    (net (code "108") (name "unconnected-(U1A-PD0-PadCN11_57)") (class "Default")
      (node (ref "U1") (pin "CN11_57") (pinfunction "PD0_CN11_57") (pintype "bidirectional"))
    )
    (net (code "109") (name "unconnected-(U1A-PD1-PadCN11_55)") (class "Default")
      (node (ref "U1") (pin "CN11_55") (pinfunction "PD1_CN11_55") (pintype "bidirectional"))
    )
    (net (code "110") (name "unconnected-(U1A-PD2-PadCN11_4)") (class "Default")
      (node (ref "U1") (pin "CN11_4") (pinfunction "PD2_CN11_4") (pintype "bidirectional"))
    )
    (net (code "111") (name "unconnected-(U1A-PD3-PadCN11_40)") (class "Default")
      (node (ref "U1") (pin "CN11_40") (pinfunction "PD3_CN11_40") (pintype "bidirectional"))
    )
    (net (code "112") (name "unconnected-(U1A-PD4-PadCN11_39)") (class "Default")
      (node (ref "U1") (pin "CN11_39") (pinfunction "PD4_CN11_39") (pintype "bidirectional"))
    )
    (net (code "113") (name "unconnected-(U1A-PD7-PadCN11_45)") (class "Default")
      (node (ref "U1") (pin "CN11_45") (pinfunction "PD7_CN11_45") (pintype "bidirectional"))
    )
    (net (code "114") (name "unconnected-(U1A-PD9-PadCN11_69)") (class "Default")
      (node (ref "U1") (pin "CN11_69") (pinfunction "PD9_CN11_69") (pintype "bidirectional"))
    )
    (net (code "115") (name "unconnected-(U1A-PE1-PadCN11_61)") (class "Default")
      (node (ref "U1") (pin "CN11_61") (pinfunction "PE1_CN11_61") (pintype "bidirectional"))
    )
    (net (code "116") (name "unconnected-(U1A-PE2-PadCN11_46)") (class "Default")
      (node (ref "U1") (pin "CN11_46") (pinfunction "PE2_CN11_46") (pintype "bidirectional"))
    )
    (net (code "117") (name "unconnected-(U1A-PE3-PadCN11_47)") (class "Default")
      (node (ref "U1") (pin "CN11_47") (pinfunction "PE3_CN11_47") (pintype "bidirectional"))
    )
    (net (code "118") (name "unconnected-(U1A-PE4-PadCN11_48)") (class "Default")
      (node (ref "U1") (pin "CN11_48") (pinfunction "PE4_CN11_48") (pintype "bidirectional"))
    )
    (net (code "119") (name "unconnected-(U1A-PE5-PadCN11_50)") (class "Default")
      (node (ref "U1") (pin "CN11_50") (pinfunction "PE5_CN11_50") (pintype "bidirectional"))
    )
    (net (code "120") (name "unconnected-(U1A-PE6-PadCN11_62)") (class "Default")
      (node (ref "U1") (pin "CN11_62") (pinfunction "PE6_CN11_62") (pintype "bidirectional"))
    )
    (net (code "121") (name "unconnected-(U1A-PF0-PadCN11_53)") (class "Default")
      (node (ref "U1") (pin "CN11_53") (pinfunction "PF0_CN11_53") (pintype "bidirectional"))
    )
    (net (code "122") (name "unconnected-(U1A-PF1-PadCN11_51)") (class "Default")
      (node (ref "U1") (pin "CN11_51") (pinfunction "PF1_CN11_51") (pintype "bidirectional"))
    )
    (net (code "123") (name "unconnected-(U1A-PF2-PadCN11_52)") (class "Default")
      (node (ref "U1") (pin "CN11_52") (pinfunction "PF2_CN11_52") (pintype "bidirectional"))
    )
    (net (code "124") (name "unconnected-(U1A-PF6-PadCN11_9)") (class "Default")
      (node (ref "U1") (pin "CN11_9") (pinfunction "PF6_CN11_9") (pintype "bidirectional"))
    )
    (net (code "125") (name "unconnected-(U1A-PF7-PadCN11_11)") (class "Default")
      (node (ref "U1") (pin "CN11_11") (pinfunction "PF7_CN11_11") (pintype "bidirectional"))
    )
    (net (code "126") (name "unconnected-(U1A-PF8-PadCN11_54)") (class "Default")
      (node (ref "U1") (pin "CN11_54") (pinfunction "PF8_CN11_54") (pintype "bidirectional"))
    )
    (net (code "127") (name "unconnected-(U1A-PF9-PadCN11_56)") (class "Default")
      (node (ref "U1") (pin "CN11_56") (pinfunction "PF9_CN11_56") (pintype "bidirectional"))
    )
    (net (code "128") (name "unconnected-(U1A-PG0-PadCN11_59)") (class "Default")
      (node (ref "U1") (pin "CN11_59") (pinfunction "PG0_CN11_59") (pintype "bidirectional"))
    )
    (net (code "129") (name "unconnected-(U1A-PG1-PadCN11_58)") (class "Default")
      (node (ref "U1") (pin "CN11_58") (pinfunction "PG1_CN11_58") (pintype "bidirectional"))
    )
    (net (code "130") (name "unconnected-(U1A-PG2-PadCN11_42)") (class "Default")
      (node (ref "U1") (pin "CN11_42") (pinfunction "PG2_CN11_42") (pintype "bidirectional"))
    )
    (net (code "131") (name "unconnected-(U1A-PG3-PadCN11_44)") (class "Default")
      (node (ref "U1") (pin "CN11_44") (pinfunction "PG3_CN11_44") (pintype "bidirectional"))
    )
    (net (code "132") (name "unconnected-(U1A-PG10-PadCN11_66)") (class "Default")
      (node (ref "U1") (pin "CN11_66") (pinfunction "PG10_CN11_66") (pintype "bidirectional"))
    )
    (net (code "133") (name "unconnected-(U1A-PG11-PadCN11_70)") (class "Default")
      (node (ref "U1") (pin "CN11_70") (pinfunction "PG11_CN11_70") (pintype "bidirectional"))
    )
    (net (code "134") (name "unconnected-(U1A-PG13-PadCN11_68)") (class "Default")
      (node (ref "U1") (pin "CN11_68") (pinfunction "PG13_CN11_68") (pintype "bidirectional"))
    )
    (net (code "135") (name "unconnected-(U1A-PG15-PadCN11_64)") (class "Default")
      (node (ref "U1") (pin "CN11_64") (pinfunction "PG15_CN11_64") (pintype "bidirectional"))
    )
    (net (code "136") (name "unconnected-(U1A-PH0-PadCN11_29)") (class "Default")
      (node (ref "U1") (pin "CN11_29") (pinfunction "PH0_CN11_29") (pintype "bidirectional"))
    )
    (net (code "137") (name "unconnected-(U1A-PH1-PadCN11_31)") (class "Default")
      (node (ref "U1") (pin "CN11_31") (pinfunction "PH1_CN11_31") (pintype "bidirectional"))
    )
    (net (code "138") (name "unconnected-(U1A-VBAT-PadCN11_33)") (class "Default")
      (node (ref "U1") (pin "CN11_33") (pinfunction "VBAT_CN11_33") (pintype "power_in"))
    )
    (net (code "139") (name "unconnected-(U1A-VIN-PadCN11_24)") (class "Default")
      (node (ref "U1") (pin "CN11_24") (pinfunction "VIN_CN11_24") (pintype "power_in"))
    )
    (net (code "140") (name "unconnected-(U1B-5V_USB_STLK-PadCN12_8)") (class "Default")
      (node (ref "U1") (pin "CN12_8") (pinfunction "5V_USB_STLK_CN12_8") (pintype "power_in"))
    )
    (net (code "141") (name "unconnected-(U1B-AGND_CN12-PadCN12_32)") (class "Default")
      (node (ref "U1") (pin "CN12_32") (pinfunction "AGND_CN12_CN12_32") (pintype "power_in"))
    )
    (net (code "142") (name "unconnected-(U1B-GND_CN12-PadCN12_9)") (class "Default")
      (node (ref "U1") (pin "CN12_9") (pinfunction "GND_CN12_CN12_9") (pintype "power_in"))
    )
    (net (code "143") (name "unconnected-(U1B-GND_CN12-PadCN12_20)") (class "Default")
      (node (ref "U1") (pin "CN12_20") (pinfunction "GND_CN12_CN12_20") (pintype "power_in"))
    )
    (net (code "144") (name "unconnected-(U1B-GND_CN12-PadCN12_39)") (class "Default")
      (node (ref "U1") (pin "CN12_39") (pinfunction "GND_CN12_CN12_39") (pintype "power_in"))
    )
    (net (code "145") (name "unconnected-(U1B-GND_CN12-PadCN12_54)") (class "Default")
      (node (ref "U1") (pin "CN12_54") (pinfunction "GND_CN12_CN12_54") (pintype "power_in"))
    )
    (net (code "146") (name "unconnected-(U1B-GND_CN12-PadCN12_63)") (class "Default")
      (node (ref "U1") (pin "CN12_63") (pinfunction "GND_CN12_CN12_63") (pintype "power_in"))
    )
    (net (code "147") (name "unconnected-(U1B-PA5-PadCN12_11)") (class "Default")
      (node (ref "U1") (pin "CN12_11") (pinfunction "PA5_CN12_11") (pintype "bidirectional"))
    )
    (net (code "148") (name "unconnected-(U1B-PA7-PadCN12_15)") (class "Default")
      (node (ref "U1") (pin "CN12_15") (pinfunction "PA7_CN12_15") (pintype "bidirectional"))
    )
    (net (code "149") (name "unconnected-(U1B-PA9-PadCN12_21)") (class "Default")
      (node (ref "U1") (pin "CN12_21") (pinfunction "PA9_CN12_21") (pintype "bidirectional"))
    )
    (net (code "150") (name "unconnected-(U1B-PA10-PadCN12_33)") (class "Default")
      (node (ref "U1") (pin "CN12_33") (pinfunction "PA10_CN12_33") (pintype "bidirectional"))
    )
    (net (code "151") (name "unconnected-(U1B-PA11-PadCN12_14)") (class "Default")
      (node (ref "U1") (pin "CN12_14") (pinfunction "PA11_CN12_14") (pintype "bidirectional"))
    )
    (net (code "152") (name "unconnected-(U1B-PA12-PadCN12_12)") (class "Default")
      (node (ref "U1") (pin "CN12_12") (pinfunction "PA12_CN12_12") (pintype "bidirectional"))
    )
    (net (code "153") (name "unconnected-(U1B-PB2-PadCN12_22)") (class "Default")
      (node (ref "U1") (pin "CN12_22") (pinfunction "PB2_CN12_22") (pintype "bidirectional"))
    )
    (net (code "154") (name "unconnected-(U1B-PB3-PadCN12_31)") (class "Default")
      (node (ref "U1") (pin "CN12_31") (pinfunction "PB3_CN12_31") (pintype "bidirectional"))
    )
    (net (code "155") (name "unconnected-(U1B-PB12-PadCN12_16)") (class "Default")
      (node (ref "U1") (pin "CN12_16") (pinfunction "PB12_CN12_16") (pintype "bidirectional"))
    )
    (net (code "156") (name "unconnected-(U1B-PB13-PadCN12_30)") (class "Default")
      (node (ref "U1") (pin "CN12_30") (pinfunction "PB13_CN12_30") (pintype "bidirectional"))
    )
    (net (code "157") (name "unconnected-(U1B-PB14-PadCN12_28)") (class "Default")
      (node (ref "U1") (pin "CN12_28") (pinfunction "PB14_CN12_28") (pintype "bidirectional"))
    )
    (net (code "158") (name "unconnected-(U1B-PB15-PadCN12_26)") (class "Default")
      (node (ref "U1") (pin "CN12_26") (pinfunction "PB15_CN12_26") (pintype "bidirectional"))
    )
    (net (code "159") (name "unconnected-(U1B-PC4-PadCN12_34)") (class "Default")
      (node (ref "U1") (pin "CN12_34") (pinfunction "PC4_CN12_34") (pintype "bidirectional"))
    )
    (net (code "160") (name "unconnected-(U1B-PC5-PadCN12_6)") (class "Default")
      (node (ref "U1") (pin "CN12_6") (pinfunction "PC5_CN12_6") (pintype "bidirectional"))
    )
    (net (code "161") (name "unconnected-(U1B-PC6-PadCN12_4)") (class "Default")
      (node (ref "U1") (pin "CN12_4") (pinfunction "PC6_CN12_4") (pintype "bidirectional"))
    )
    (net (code "162") (name "unconnected-(U1B-PC8-PadCN12_2)") (class "Default")
      (node (ref "U1") (pin "CN12_2") (pinfunction "PC8_CN12_2") (pintype "bidirectional"))
    )
    (net (code "163") (name "unconnected-(U1B-PC9-PadCN12_1)") (class "Default")
      (node (ref "U1") (pin "CN12_1") (pinfunction "PC9_CN12_1") (pintype "bidirectional"))
    )
    (net (code "164") (name "unconnected-(U1B-PD8-PadCN12_10)") (class "Default")
      (node (ref "U1") (pin "CN12_10") (pinfunction "PD8_CN12_10") (pintype "bidirectional"))
    )
    (net (code "165") (name "unconnected-(U1B-PD10-PadCN12_65)") (class "Default")
      (node (ref "U1") (pin "CN12_65") (pinfunction "PD10_CN12_65") (pintype "bidirectional"))
    )
    (net (code "166") (name "unconnected-(U1B-PD11-PadCN12_45)") (class "Default")
      (node (ref "U1") (pin "CN12_45") (pinfunction "PD11_CN12_45") (pintype "bidirectional"))
    )
    (net (code "167") (name "unconnected-(U1B-PE0-PadCN12_64)") (class "Default")
      (node (ref "U1") (pin "CN12_64") (pinfunction "PE0_CN12_64") (pintype "bidirectional"))
    )
    (net (code "168") (name "unconnected-(U1B-PE7-PadCN12_44)") (class "Default")
      (node (ref "U1") (pin "CN12_44") (pinfunction "PE7_CN12_44") (pintype "bidirectional"))
    )
    (net (code "169") (name "unconnected-(U1B-PE8-PadCN12_40)") (class "Default")
      (node (ref "U1") (pin "CN12_40") (pinfunction "PE8_CN12_40") (pintype "bidirectional"))
    )
    (net (code "170") (name "unconnected-(U1B-PE9-PadCN12_52)") (class "Default")
      (node (ref "U1") (pin "CN12_52") (pinfunction "PE9_CN12_52") (pintype "bidirectional"))
    )
    (net (code "171") (name "unconnected-(U1B-PE10-PadCN12_47)") (class "Default")
      (node (ref "U1") (pin "CN12_47") (pinfunction "PE10_CN12_47") (pintype "bidirectional"))
    )
    (net (code "172") (name "unconnected-(U1B-PE11-PadCN12_56)") (class "Default")
      (node (ref "U1") (pin "CN12_56") (pinfunction "PE11_CN12_56") (pintype "bidirectional"))
    )
    (net (code "173") (name "unconnected-(U1B-PE12-PadCN12_49)") (class "Default")
      (node (ref "U1") (pin "CN12_49") (pinfunction "PE12_CN12_49") (pintype "bidirectional"))
    )
    (net (code "174") (name "unconnected-(U1B-PE14-PadCN12_51)") (class "Default")
      (node (ref "U1") (pin "CN12_51") (pinfunction "PE14_CN12_51") (pintype "bidirectional"))
    )
    (net (code "175") (name "unconnected-(U1B-PE15-PadCN12_53)") (class "Default")
      (node (ref "U1") (pin "CN12_53") (pinfunction "PE15_CN12_53") (pintype "bidirectional"))
    )
    (net (code "176") (name "unconnected-(U1B-PF3-PadCN12_58)") (class "Default")
      (node (ref "U1") (pin "CN12_58") (pinfunction "PF3_CN12_58") (pintype "bidirectional"))
    )
    (net (code "177") (name "unconnected-(U1B-PF4-PadCN12_38)") (class "Default")
      (node (ref "U1") (pin "CN12_38") (pinfunction "PF4_CN12_38") (pintype "bidirectional"))
    )
    (net (code "178") (name "unconnected-(U1B-PF5-PadCN12_36)") (class "Default")
      (node (ref "U1") (pin "CN12_36") (pinfunction "PF5_CN12_36") (pintype "bidirectional"))
    )
    (net (code "179") (name "unconnected-(U1B-PF10-PadCN12_42)") (class "Default")
      (node (ref "U1") (pin "CN12_42") (pinfunction "PF10_CN12_42") (pintype "bidirectional"))
    )
    (net (code "180") (name "unconnected-(U1B-PF12-PadCN12_59)") (class "Default")
      (node (ref "U1") (pin "CN12_59") (pinfunction "PF12_CN12_59") (pintype "bidirectional"))
    )
    (net (code "181") (name "unconnected-(U1B-PF13-PadCN12_57)") (class "Default")
      (node (ref "U1") (pin "CN12_57") (pinfunction "PF13_CN12_57") (pintype "bidirectional"))
    )
    (net (code "182") (name "unconnected-(U1B-PG4-PadCN12_69)") (class "Default")
      (node (ref "U1") (pin "CN12_69") (pinfunction "PG4_CN12_69") (pintype "bidirectional"))
    )
    (net (code "183") (name "unconnected-(U1B-PG5-PadCN12_68)") (class "Default")
      (node (ref "U1") (pin "CN12_68") (pinfunction "PG5_CN12_68") (pintype "bidirectional"))
    )
    (net (code "184") (name "unconnected-(U1B-PG6-PadCN12_70)") (class "Default")
      (node (ref "U1") (pin "CN12_70") (pinfunction "PG6_CN12_70") (pintype "bidirectional"))
    )
    (net (code "185") (name "unconnected-(U1B-PG7-PadCN12_67)") (class "Default")
      (node (ref "U1") (pin "CN12_67") (pinfunction "PG7_CN12_67") (pintype "bidirectional"))
    )
    (net (code "186") (name "unconnected-(U1B-PG8-PadCN12_66)") (class "Default")
      (node (ref "U1") (pin "CN12_66") (pinfunction "PG8_CN12_66") (pintype "bidirectional"))
    )
    (net (code "187") (name "unconnected-(U1B-VREFP-PadCN12_7)") (class "Default")
      (node (ref "U1") (pin "CN12_7") (pinfunction "VREFP_CN12_7") (pintype "power_in"))
    )
    (net (code "188") (name "unconnected-(U1C-D43{slash}SDMMC_D0-PadCN8_2)") (class "Default")
      (node (ref "U1") (pin "CN8_2") (pinfunction "D43/SDMMC_D0_CN8_2") (pintype "bidirectional"))
    )
    (net (code "189") (name "unconnected-(U1C-D44{slash}SDMMC_D1{slash}I2S_A_CKIN-PadCN8_4)") (class "Default")
      (node (ref "U1") (pin "CN8_4") (pinfunction "D44/SDMMC_D1/I2S_A_CKIN_CN8_4") (pintype "bidirectional"))
    )
    (net (code "190") (name "unconnected-(U1C-D45{slash}SDMMC_D2-PadCN8_6)") (class "Default")
      (node (ref "U1") (pin "CN8_6") (pinfunction "D45/SDMMC_D2_CN8_6") (pintype "bidirectional"))
    )
    (net (code "191") (name "unconnected-(U1C-D46{slash}SDMMC_D3-PadCN8_8)") (class "Default")
      (node (ref "U1") (pin "CN8_8") (pinfunction "D46/SDMMC_D3_CN8_8") (pintype "bidirectional"))
    )
    (net (code "192") (name "unconnected-(U1C-D47{slash}SDMMC_CK-PadCN8_10)") (class "Default")
      (node (ref "U1") (pin "CN8_10") (pinfunction "D47/SDMMC_CK_CN8_10") (pintype "bidirectional"))
    )
    (net (code "193") (name "unconnected-(U1C-D48{slash}SDMMC_CMD-PadCN8_12)") (class "Default")
      (node (ref "U1") (pin "CN8_12") (pinfunction "D48/SDMMC_CMD_CN8_12") (pintype "bidirectional"))
    )
    (net (code "194") (name "unconnected-(U1C-D49{slash}IO-PadCN8_14)") (class "Default")
      (node (ref "U1") (pin "CN8_14") (pinfunction "D49/IO_CN8_14") (pintype "bidirectional"))
    )
    (net (code "195") (name "unconnected-(U1C-D50{slash}IO-PadCN8_16)") (class "Default")
      (node (ref "U1") (pin "CN8_16") (pinfunction "D50/IO_CN8_16") (pintype "bidirectional"))
    )
    (net (code "196") (name "unconnected-(U1C-GND_CN8-PadCN8_11)") (class "Default")
      (node (ref "U1") (pin "CN8_11") (pinfunction "GND_CN8_CN8_11") (pintype "power_in"))
    )
    (net (code "197") (name "unconnected-(U1C-GND_CN8-PadCN8_13)") (class "Default")
      (node (ref "U1") (pin "CN8_13") (pinfunction "GND_CN8_CN8_13") (pintype "power_in"))
    )
    (net (code "198") (name "unconnected-(U1C-IOREF_CN8-PadCN8_3)") (class "Default")
      (node (ref "U1") (pin "CN8_3") (pinfunction "IOREF_CN8_CN8_3") (pintype "bidirectional"))
    )
    (net (code "199") (name "unconnected-(U1C-NC_CN8-PadCN8_1)") (class "Default")
      (node (ref "U1") (pin "CN8_1") (pinfunction "NC_CN8_CN8_1") (pintype "passive"))
    )
    (net (code "200") (name "unconnected-(U1C-NRST_CN8-PadCN8_5)") (class "Default")
      (node (ref "U1") (pin "CN8_5") (pinfunction "NRST_CN8_CN8_5") (pintype "input"))
    )
    (net (code "201") (name "unconnected-(U1C-VIN_CN8-PadCN8_15)") (class "Default")
      (node (ref "U1") (pin "CN8_15") (pinfunction "VIN_CN8_CN8_15") (pintype "power_in"))
    )
    (net (code "202") (name "unconnected-(U1D-A0{slash}ADC12_INP15-PadCN9_1)") (class "Default")
      (node (ref "U1") (pin "CN9_1") (pinfunction "A0/ADC12_INP15_CN9_1") (pintype "input"))
    )
    (net (code "203") (name "unconnected-(U1D-A1{slash}ADC123_INP10-PadCN9_3)") (class "Default")
      (node (ref "U1") (pin "CN9_3") (pinfunction "A1/ADC123_INP10_CN9_3") (pintype "input"))
    )
    (net (code "204") (name "unconnected-(U1D-A2{slash}ADC12_INP13-PadCN9_5)") (class "Default")
      (node (ref "U1") (pin "CN9_5") (pinfunction "A2/ADC12_INP13_CN9_5") (pintype "input"))
    )
    (net (code "205") (name "unconnected-(U1D-A3{slash}ADC12_INP5-PadCN9_7)") (class "Default")
      (node (ref "U1") (pin "CN9_7") (pinfunction "A3/ADC12_INP5_CN9_7") (pintype "input"))
    )
    (net (code "206") (name "unconnected-(U1D-A4{slash}ADC123_INP12{slash}I2C1_SDA-PadCN9_9)") (class "Default")
      (node (ref "U1") (pin "CN9_9") (pinfunction "A4/ADC123_INP12/I2C1_SDA_CN9_9") (pintype "input"))
    )
    (net (code "207") (name "unconnected-(U1D-A5{slash}ADC3_INP6{slash}I2C1_SCL-PadCN9_11)") (class "Default")
      (node (ref "U1") (pin "CN9_11") (pinfunction "A5/ADC3_INP6/I2C1_SCL_CN9_11") (pintype "input"))
    )
    (net (code "208") (name "unconnected-(U1D-D51{slash}USART_B_SCLK-PadCN9_2)") (class "Default")
      (node (ref "U1") (pin "CN9_2") (pinfunction "D51/USART_B_SCLK_CN9_2") (pintype "bidirectional"))
    )
    (net (code "209") (name "unconnected-(U1D-D52{slash}USART_B_RX-PadCN9_4)") (class "Default")
      (node (ref "U1") (pin "CN9_4") (pinfunction "D52/USART_B_RX_CN9_4") (pintype "bidirectional"))
    )
    (net (code "210") (name "unconnected-(U1D-D53{slash}USART_B_TX-PadCN9_6)") (class "Default")
      (node (ref "U1") (pin "CN9_6") (pinfunction "D53/USART_B_TX_CN9_6") (pintype "bidirectional"))
    )
    (net (code "211") (name "unconnected-(U1D-D54{slash}USART_B_RTS-PadCN9_8)") (class "Default")
      (node (ref "U1") (pin "CN9_8") (pinfunction "D54/USART_B_RTS_CN9_8") (pintype "bidirectional"))
    )
    (net (code "212") (name "unconnected-(U1D-D55{slash}USART_B_CTS-PadCN9_10)") (class "Default")
      (node (ref "U1") (pin "CN9_10") (pinfunction "D55/USART_B_CTS_CN9_10") (pintype "bidirectional"))
    )
    (net (code "213") (name "unconnected-(U1D-D56{slash}SAI_A_MCLK-PadCN9_14)") (class "Default")
      (node (ref "U1") (pin "CN9_14") (pinfunction "D56/SAI_A_MCLK_CN9_14") (pintype "bidirectional"))
    )
    (net (code "214") (name "unconnected-(U1D-D57{slash}SAI_A_FS-PadCN9_16)") (class "Default")
      (node (ref "U1") (pin "CN9_16") (pinfunction "D57/SAI_A_FS_CN9_16") (pintype "bidirectional"))
    )
    (net (code "215") (name "unconnected-(U1D-D58{slash}SAI_A_SCK-PadCN9_18)") (class "Default")
      (node (ref "U1") (pin "CN9_18") (pinfunction "D58/SAI_A_SCK_CN9_18") (pintype "bidirectional"))
    )
    (net (code "216") (name "unconnected-(U1D-D59{slash}SAI_A_SD-PadCN9_20)") (class "Default")
      (node (ref "U1") (pin "CN9_20") (pinfunction "D59/SAI_A_SD_CN9_20") (pintype "bidirectional"))
    )
    (net (code "217") (name "unconnected-(U1D-D60{slash}SAI_B_SD-PadCN9_22)") (class "Default")
      (node (ref "U1") (pin "CN9_22") (pinfunction "D60/SAI_B_SD_CN9_22") (pintype "bidirectional"))
    )
    (net (code "218") (name "unconnected-(U1D-D61{slash}SAI_B_SCK-PadCN9_24)") (class "Default")
      (node (ref "U1") (pin "CN9_24") (pinfunction "D61/SAI_B_SCK_CN9_24") (pintype "bidirectional"))
    )
    (net (code "219") (name "unconnected-(U1D-D62{slash}SAI_B_MCLK-PadCN9_26)") (class "Default")
      (node (ref "U1") (pin "CN9_26") (pinfunction "D62/SAI_B_MCLK_CN9_26") (pintype "bidirectional"))
    )
    (net (code "220") (name "unconnected-(U1D-D63{slash}SAI_B_FS-PadCN9_28)") (class "Default")
      (node (ref "U1") (pin "CN9_28") (pinfunction "D63/SAI_B_FS_CN9_28") (pintype "bidirectional"))
    )
    (net (code "221") (name "unconnected-(U1D-D64{slash}IO-PadCN9_30)") (class "Default")
      (node (ref "U1") (pin "CN9_30") (pinfunction "D64/IO_CN9_30") (pintype "bidirectional"))
    )
    (net (code "222") (name "unconnected-(U1D-D65{slash}IO-PadCN9_29)") (class "Default")
      (node (ref "U1") (pin "CN9_29") (pinfunction "D65/IO_CN9_29") (pintype "bidirectional"))
    )
    (net (code "223") (name "unconnected-(U1D-D66{slash}CAN_TX-PadCN9_27)") (class "Default")
      (node (ref "U1") (pin "CN9_27") (pinfunction "D66/CAN_TX_CN9_27") (pintype "output"))
    )
    (net (code "224") (name "unconnected-(U1D-D67{slash}CAN_RX-PadCN9_25)") (class "Default")
      (node (ref "U1") (pin "CN9_25") (pinfunction "D67/CAN_RX_CN9_25") (pintype "input"))
    )
    (net (code "225") (name "unconnected-(U1D-D68{slash}I2C_B_SDA-PadCN9_21)") (class "Default")
      (node (ref "U1") (pin "CN9_21") (pinfunction "D68/I2C_B_SDA_CN9_21") (pintype "bidirectional"))
    )
    (net (code "226") (name "unconnected-(U1D-D69{slash}I2C_B_SCL-PadCN9_19)") (class "Default")
      (node (ref "U1") (pin "CN9_19") (pinfunction "D69/I2C_B_SCL_CN9_19") (pintype "bidirectional"))
    )
    (net (code "227") (name "unconnected-(U1D-D70{slash}I2C_B_SMBA-PadCN9_17)") (class "Default")
      (node (ref "U1") (pin "CN9_17") (pinfunction "D70/I2C_B_SMBA_CN9_17") (pintype "bidirectional"))
    )
    (net (code "228") (name "unconnected-(U1D-D71{slash}COMP2_INP-PadCN9_15)") (class "Default")
      (node (ref "U1") (pin "CN9_15") (pinfunction "D71/COMP2_INP_CN9_15") (pintype "bidirectional"))
    )
    (net (code "229") (name "unconnected-(U1D-D72{slash}COMP1_INP-PadCN9_13)") (class "Default")
      (node (ref "U1") (pin "CN9_13") (pinfunction "D72/COMP1_INP_CN9_13") (pintype "bidirectional"))
    )
    (net (code "230") (name "unconnected-(U1D-GND_CN9-PadCN9_12)") (class "Default")
      (node (ref "U1") (pin "CN9_12") (pinfunction "GND_CN9_CN9_12") (pintype "power_in"))
    )
    (net (code "231") (name "unconnected-(U1D-GND_CN9-PadCN9_23)") (class "Default")
      (node (ref "U1") (pin "CN9_23") (pinfunction "GND_CN9_CN9_23") (pintype "power_in"))
    )
    (net (code "232") (name "unconnected-(U1E-D8{slash}IO-PadCN7_20)") (class "Default")
      (node (ref "U1") (pin "CN7_20") (pinfunction "D8/IO_CN7_20") (pintype "bidirectional"))
    )
    (net (code "233") (name "unconnected-(U1E-D9{slash}TIMER_B_PWM2-PadCN7_18)") (class "Default")
      (node (ref "U1") (pin "CN7_18") (pinfunction "D9/TIMER_B_PWM2_CN7_18") (pintype "bidirectional"))
    )
    (net (code "234") (name "unconnected-(U1E-D10{slash}SPI_A_CS{slash}TIM_B_PWM3-PadCN7_16)") (class "Default")
      (node (ref "U1") (pin "CN7_16") (pinfunction "D10/SPI_A_CS/TIM_B_PWM3_CN7_16") (pintype "bidirectional"))
    )
    (net (code "235") (name "unconnected-(U1E-D11{slash}SPI_A_MOSI{slash}TIM_E_PWM1-PadCN7_14)") (class "Default")
      (node (ref "U1") (pin "CN7_14") (pinfunction "D11/SPI_A_MOSI/TIM_E_PWM1_CN7_14") (pintype "bidirectional"))
    )
    (net (code "236") (name "unconnected-(U1E-D12{slash}SPI_A_MISO-PadCN7_12)") (class "Default")
      (node (ref "U1") (pin "CN7_12") (pinfunction "D12/SPI_A_MISO_CN7_12") (pintype "bidirectional"))
    )
    (net (code "237") (name "unconnected-(U1E-D13{slash}SPI_A_SCK-PadCN7_10)") (class "Default")
      (node (ref "U1") (pin "CN7_10") (pinfunction "D13/SPI_A_SCK_CN7_10") (pintype "bidirectional"))
    )
    (net (code "238") (name "unconnected-(U1E-D14{slash}I2C_A_SDA-PadCN7_4)") (class "Default")
      (node (ref "U1") (pin "CN7_4") (pinfunction "D14/I2C_A_SDA_CN7_4") (pintype "bidirectional"))
    )
    (net (code "239") (name "unconnected-(U1E-D15{slash}I2C_A_SCL-PadCN7_2)") (class "Default")
      (node (ref "U1") (pin "CN7_2") (pinfunction "D15/I2C_A_SCL_CN7_2") (pintype "bidirectional"))
    )
    (net (code "240") (name "unconnected-(U1E-D16{slash}I2S_A_MCK-PadCN7_1)") (class "Default")
      (node (ref "U1") (pin "CN7_1") (pinfunction "D16/I2S_A_MCK_CN7_1") (pintype "bidirectional"))
    )
    (net (code "241") (name "unconnected-(U1E-D17{slash}I2S_A_SD-PadCN7_3)") (class "Default")
      (node (ref "U1") (pin "CN7_3") (pinfunction "D17/I2S_A_SD_CN7_3") (pintype "bidirectional"))
    )
    (net (code "242") (name "unconnected-(U1E-D18{slash}I2S_A_CK-PadCN7_5)") (class "Default")
      (node (ref "U1") (pin "CN7_5") (pinfunction "D18/I2S_A_CK_CN7_5") (pintype "bidirectional"))
    )
    (net (code "243") (name "unconnected-(U1E-D19{slash}I2S_A_WS-PadCN7_7)") (class "Default")
      (node (ref "U1") (pin "CN7_7") (pinfunction "D19/I2S_A_WS_CN7_7") (pintype "bidirectional"))
    )
    (net (code "244") (name "unconnected-(U1E-D20{slash}I2S_B_WS-PadCN7_9)") (class "Default")
      (node (ref "U1") (pin "CN7_9") (pinfunction "D20/I2S_B_WS_CN7_9") (pintype "bidirectional"))
    )
    (net (code "245") (name "unconnected-(U1E-D21{slash}I2S_B_MCK-PadCN7_11)") (class "Default")
      (node (ref "U1") (pin "CN7_11") (pinfunction "D21/I2S_B_MCK_CN7_11") (pintype "bidirectional"))
    )
    (net (code "246") (name "unconnected-(U1E-D22{slash}I2S_B_SD{slash}SPI_B_MOSI-PadCN7_13)") (class "Default")
      (node (ref "U1") (pin "CN7_13") (pinfunction "D22/I2S_B_SD/SPI_B_MOSI_CN7_13") (pintype "bidirectional"))
    )
    (net (code "247") (name "unconnected-(U1E-D23{slash}I2S_B_CK{slash}SPI_B_SCK-PadCN7_15)") (class "Default")
      (node (ref "U1") (pin "CN7_15") (pinfunction "D23/I2S_B_CK/SPI_B_SCK_CN7_15") (pintype "bidirectional"))
    )
    (net (code "248") (name "unconnected-(U1E-D24{slash}SPI_B_NSS-PadCN7_17)") (class "Default")
      (node (ref "U1") (pin "CN7_17") (pinfunction "D24/SPI_B_NSS_CN7_17") (pintype "bidirectional"))
    )
    (net (code "249") (name "unconnected-(U1E-D25{slash}SPI_B_MISO-PadCN7_19)") (class "Default")
      (node (ref "U1") (pin "CN7_19") (pinfunction "D25/SPI_B_MISO_CN7_19") (pintype "bidirectional"))
    )
    (net (code "250") (name "unconnected-(U1E-GND_CN7-PadCN7_8)") (class "Default")
      (node (ref "U1") (pin "CN7_8") (pinfunction "GND_CN7_CN7_8") (pintype "power_in"))
    )
    (net (code "251") (name "unconnected-(U1E-VREFP_CN7-PadCN7_6)") (class "Default")
      (node (ref "U1") (pin "CN7_6") (pinfunction "VREFP_CN7_CN7_6") (pintype "power_in"))
    )
    (net (code "252") (name "unconnected-(U1F-A6{slash}ADC_A_IN-PadCN10_7)") (class "Default")
      (node (ref "U1") (pin "CN10_7") (pinfunction "A6/ADC_A_IN_CN10_7") (pintype "input"))
    )
    (net (code "253") (name "unconnected-(U1F-A7{slash}ADC_B_IN-PadCN10_9)") (class "Default")
      (node (ref "U1") (pin "CN10_9") (pinfunction "A7/ADC_B_IN_CN10_9") (pintype "input"))
    )
    (net (code "254") (name "unconnected-(U1F-A8{slash}ADC_C_IN-PadCN10_11)") (class "Default")
      (node (ref "U1") (pin "CN10_11") (pinfunction "A8/ADC_C_IN_CN10_11") (pintype "input"))
    )
    (net (code "255") (name "unconnected-(U1F-AGND_CN10-PadCN10_3)") (class "Default")
      (node (ref "U1") (pin "CN10_3") (pinfunction "AGND_CN10_CN10_3") (pintype "power_in"))
    )
    (net (code "256") (name "unconnected-(U1F-AVDD-PadCN10_1)") (class "Default")
      (node (ref "U1") (pin "CN10_1") (pinfunction "AVDD_CN10_1") (pintype "power_in"))
    )
    (net (code "257") (name "unconnected-(U1F-D0{slash}USART_A_RX-PadCN10_16)") (class "Default")
      (node (ref "U1") (pin "CN10_16") (pinfunction "D0/USART_A_RX_CN10_16") (pintype "input"))
    )
    (net (code "258") (name "unconnected-(U1F-D1{slash}USART_A_TX-PadCN10_14)") (class "Default")
      (node (ref "U1") (pin "CN10_14") (pinfunction "D1/USART_A_TX_CN10_14") (pintype "output"))
    )
    (net (code "259") (name "unconnected-(U1F-D2{slash}IO-PadCN10_12)") (class "Default")
      (node (ref "U1") (pin "CN10_12") (pinfunction "D2/IO_CN10_12") (pintype "bidirectional"))
    )
    (net (code "260") (name "unconnected-(U1F-D3{slash}TIMER_A_PWM3-PadCN10_10)") (class "Default")
      (node (ref "U1") (pin "CN10_10") (pinfunction "D3/TIMER_A_PWM3_CN10_10") (pintype "bidirectional"))
    )
    (net (code "261") (name "unconnected-(U1F-D4{slash}IO-PadCN10_8)") (class "Default")
      (node (ref "U1") (pin "CN10_8") (pinfunction "D4/IO_CN10_8") (pintype "bidirectional"))
    )
    (net (code "262") (name "unconnected-(U1F-D5{slash}TIMER_A_PWM2-PadCN10_6)") (class "Default")
      (node (ref "U1") (pin "CN10_6") (pinfunction "D5/TIMER_A_PWM2_CN10_6") (pintype "bidirectional"))
    )
    (net (code "263") (name "unconnected-(U1F-D6{slash}TIMER_A_PWM1-PadCN10_4)") (class "Default")
      (node (ref "U1") (pin "CN10_4") (pinfunction "D6/TIMER_A_PWM1_CN10_4") (pintype "bidirectional"))
    )
    (net (code "264") (name "unconnected-(U1F-D7{slash}IO-PadCN10_2)") (class "Default")
      (node (ref "U1") (pin "CN10_2") (pinfunction "D7/IO_CN10_2") (pintype "bidirectional"))
    )
    (net (code "265") (name "unconnected-(U1F-D26{slash}QSPI_CS-PadCN10_13)") (class "Default")
      (node (ref "U1") (pin "CN10_13") (pinfunction "D26/QSPI_CS_CN10_13") (pintype "bidirectional"))
    )
    (net (code "266") (name "unconnected-(U1F-D27{slash}QSPI_CLK-PadCN10_15)") (class "Default")
      (node (ref "U1") (pin "CN10_15") (pinfunction "D27/QSPI_CLK_CN10_15") (pintype "bidirectional"))
    )
    (net (code "267") (name "unconnected-(U1F-D28{slash}QSPI_BK1_IO3-PadCN10_19)") (class "Default")
      (node (ref "U1") (pin "CN10_19") (pinfunction "D28/QSPI_BK1_IO3_CN10_19") (pintype "bidirectional"))
    )
    (net (code "268") (name "unconnected-(U1F-D29{slash}QSPI_BK1_IO1-PadCN10_21)") (class "Default")
      (node (ref "U1") (pin "CN10_21") (pinfunction "D29/QSPI_BK1_IO1_CN10_21") (pintype "bidirectional"))
    )
    (net (code "269") (name "unconnected-(U1F-D30{slash}QSPI_BK1_IO0-PadCN10_23)") (class "Default")
      (node (ref "U1") (pin "CN10_23") (pinfunction "D30/QSPI_BK1_IO0_CN10_23") (pintype "bidirectional"))
    )
    (net (code "270") (name "unconnected-(U1F-D31{slash}QSPI_BK1_IO2-PadCN10_25)") (class "Default")
      (node (ref "U1") (pin "CN10_25") (pinfunction "D31/QSPI_BK1_IO2_CN10_25") (pintype "bidirectional"))
    )
    (net (code "271") (name "unconnected-(U1F-D32{slash}TIMER_C_PWM1-PadCN10_29)") (class "Default")
      (node (ref "U1") (pin "CN10_29") (pinfunction "D32/TIMER_C_PWM1_CN10_29") (pintype "bidirectional"))
    )
    (net (code "272") (name "unconnected-(U1F-D33{slash}TIMER_D_PWM1-PadCN10_31)") (class "Default")
      (node (ref "U1") (pin "CN10_31") (pinfunction "D33/TIMER_D_PWM1_CN10_31") (pintype "bidirectional"))
    )
    (net (code "273") (name "unconnected-(U1F-D34{slash}TIMER_B_ETR-PadCN10_33)") (class "Default")
      (node (ref "U1") (pin "CN10_33") (pinfunction "D34/TIMER_B_ETR_CN10_33") (pintype "bidirectional"))
    )
    (net (code "274") (name "unconnected-(U1F-D35{slash}TIMER_C_PWM3-PadCN10_34)") (class "Default")
      (node (ref "U1") (pin "CN10_34") (pinfunction "D35/TIMER_C_PWM3_CN10_34") (pintype "bidirectional"))
    )
    (net (code "275") (name "unconnected-(U1F-D36{slash}TIMER_C_PWM2-PadCN10_32)") (class "Default")
      (node (ref "U1") (pin "CN10_32") (pinfunction "D36/TIMER_C_PWM2_CN10_32") (pintype "bidirectional"))
    )
    (net (code "276") (name "unconnected-(U1F-D37{slash}TIMER_A_BKIN1-PadCN10_30)") (class "Default")
      (node (ref "U1") (pin "CN10_30") (pinfunction "D37/TIMER_A_BKIN1_CN10_30") (pintype "bidirectional"))
    )
    (net (code "277") (name "unconnected-(U1F-D38{slash}TIMER_A_BKIN2-PadCN10_28)") (class "Default")
      (node (ref "U1") (pin "CN10_28") (pinfunction "D38/TIMER_A_BKIN2_CN10_28") (pintype "bidirectional"))
    )
    (net (code "278") (name "unconnected-(U1F-D39{slash}TIMER_A_PWM3N-PadCN10_26)") (class "Default")
      (node (ref "U1") (pin "CN10_26") (pinfunction "D39/TIMER_A_PWM3N_CN10_26") (pintype "bidirectional"))
    )
    (net (code "279") (name "unconnected-(U1F-D40{slash}TIMER_A_PWM2N-PadCN10_24)") (class "Default")
      (node (ref "U1") (pin "CN10_24") (pinfunction "D40/TIMER_A_PWM2N_CN10_24") (pintype "bidirectional"))
    )
    (net (code "280") (name "unconnected-(U1F-D41{slash}TIMER_A_ETR-PadCN10_20)") (class "Default")
      (node (ref "U1") (pin "CN10_20") (pinfunction "D41/TIMER_A_ETR_CN10_20") (pintype "bidirectional"))
    )
    (net (code "281") (name "unconnected-(U1F-D42{slash}TIMER_A_PWM1N-PadCN10_18)") (class "Default")
      (node (ref "U1") (pin "CN10_18") (pinfunction "D42/TIMER_A_PWM1N_CN10_18") (pintype "bidirectional"))
    )
    (net (code "282") (name "unconnected-(U1F-GND_CN10-PadCN10_5)") (class "Default")
      (node (ref "U1") (pin "CN10_5") (pinfunction "GND_CN10_CN10_5") (pintype "power_in"))
    )
    (net (code "283") (name "unconnected-(U1F-GND_CN10-PadCN10_17)") (class "Default")
      (node (ref "U1") (pin "CN10_17") (pinfunction "GND_CN10_CN10_17") (pintype "power_in"))
    )
    (net (code "284") (name "unconnected-(U1F-GND_CN10-PadCN10_22)") (class "Default")
      (node (ref "U1") (pin "CN10_22") (pinfunction "GND_CN10_CN10_22") (pintype "power_in"))
    )
    (net (code "285") (name "unconnected-(U1F-GND_CN10-PadCN10_27)") (class "Default")
      (node (ref "U1") (pin "CN10_27") (pinfunction "GND_CN10_CN10_27") (pintype "power_in"))
    )
    (net (code "286") (name "unconnected-(U30-NC-Pad12)") (class "Default")
      (node (ref "U30") (pin "12") (pinfunction "NC_12") (pintype "passive"))
    )
    (net (code "287") (name "unconnected-(U31-NC-Pad12)") (class "Default")
      (node (ref "U31") (pin "12") (pinfunction "NC_12") (pintype "passive"))
    )
    (net (code "288") (name "unconnected-(U32-NC-Pad12)") (class "Default")
      (node (ref "U32") (pin "12") (pinfunction "NC_12") (pintype "passive"))
    )
    (net (code "289") (name "unconnected-(U33-NC-Pad12)") (class "Default")
      (node (ref "U33") (pin "12") (pinfunction "NC_12") (pintype "passive"))
    )
    (net (code "290") (name "unconnected-(U34-NC-Pad12)") (class "Default")
      (node (ref "U34") (pin "12") (pinfunction "NC_12") (pintype "passive"))
    )
  )
)
